# protestSign.net
KiCad netlist of a schematic drawn in EAGLE
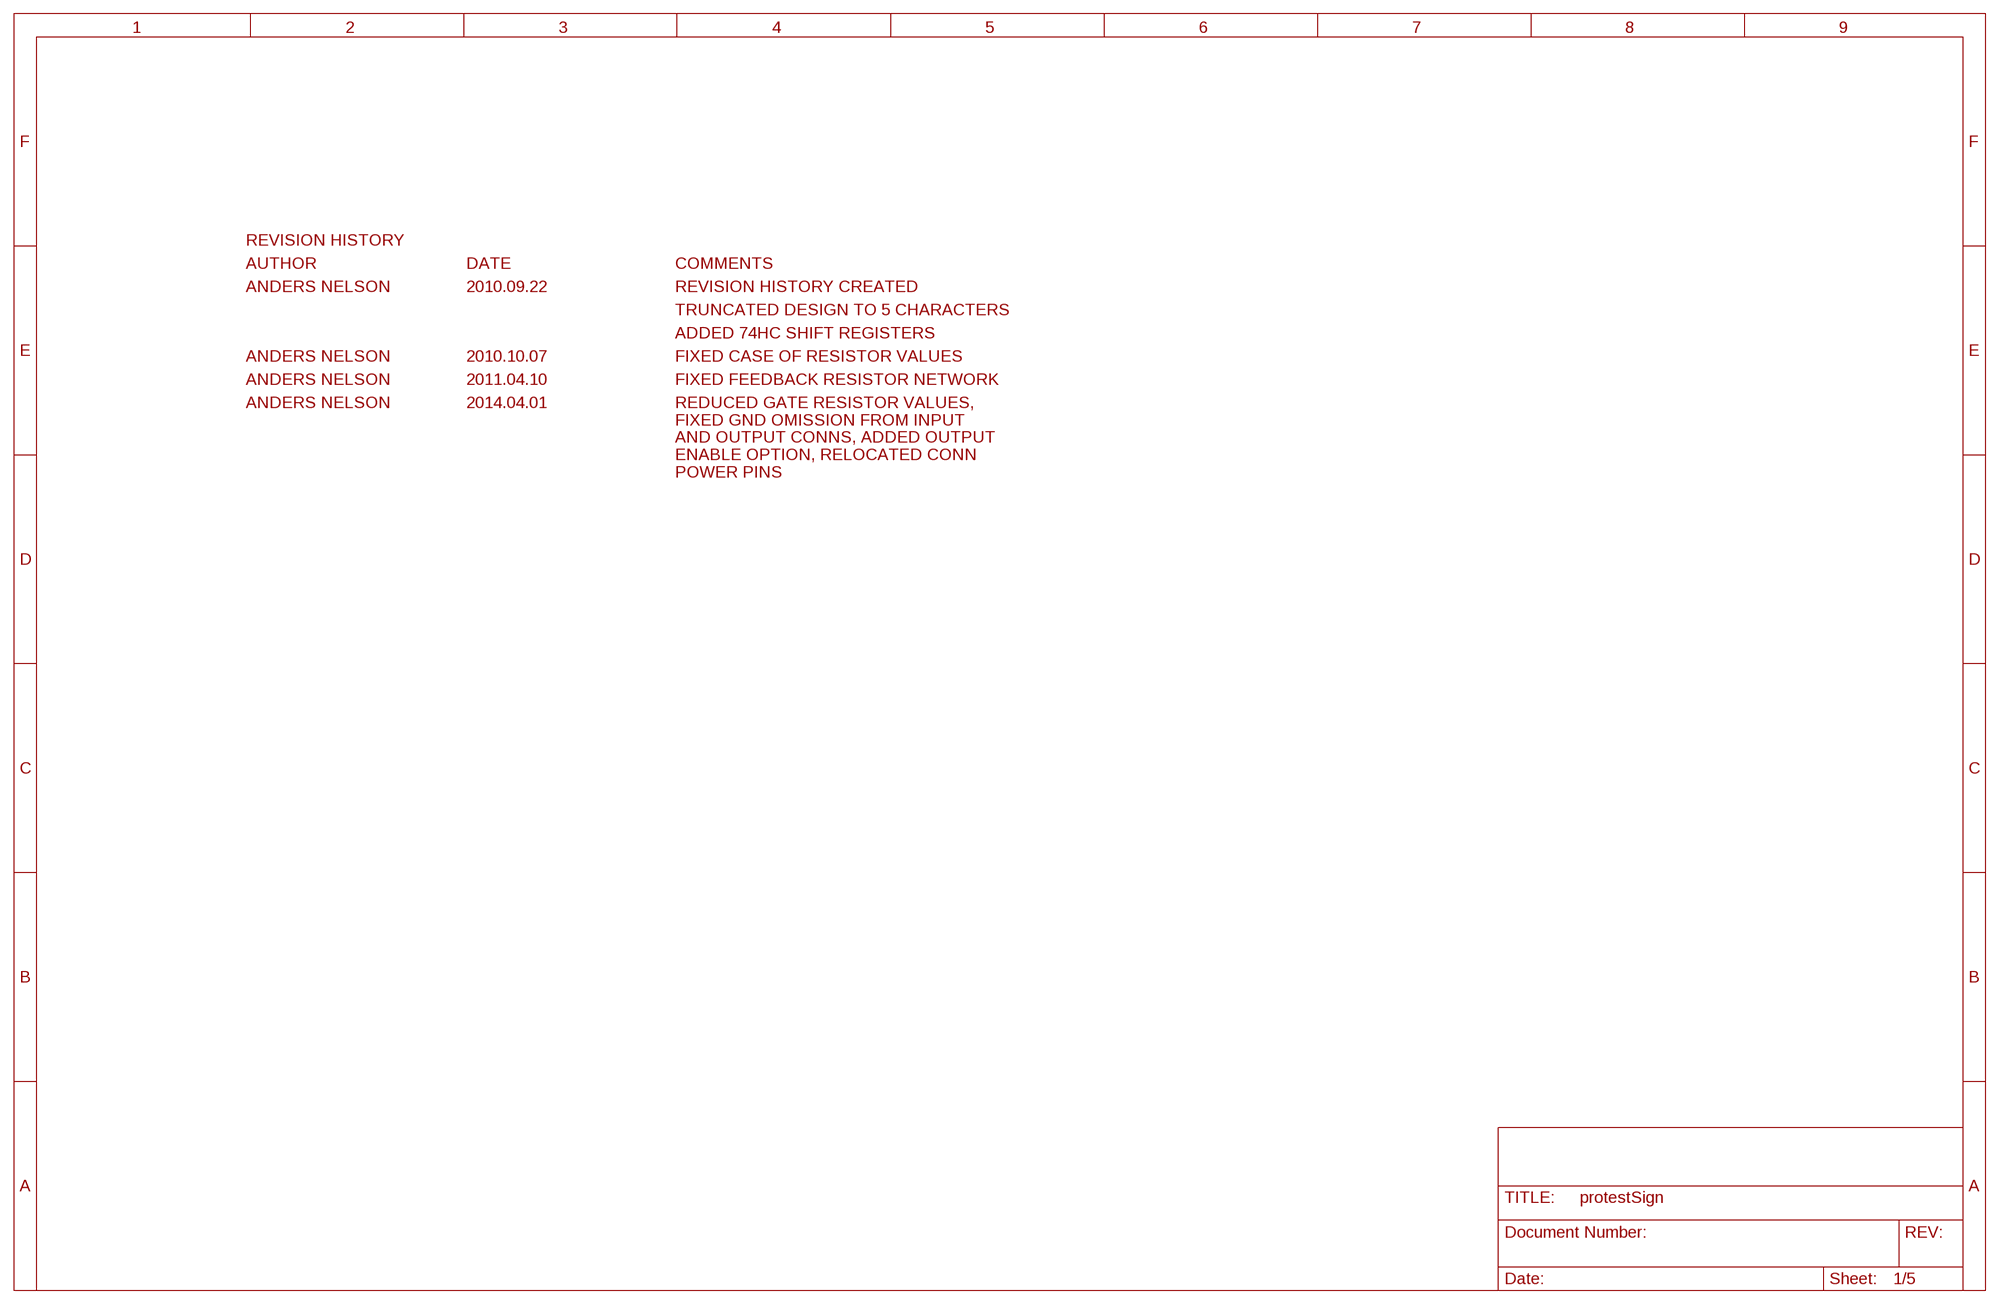
[diagram p0: schematic, sheet 1]
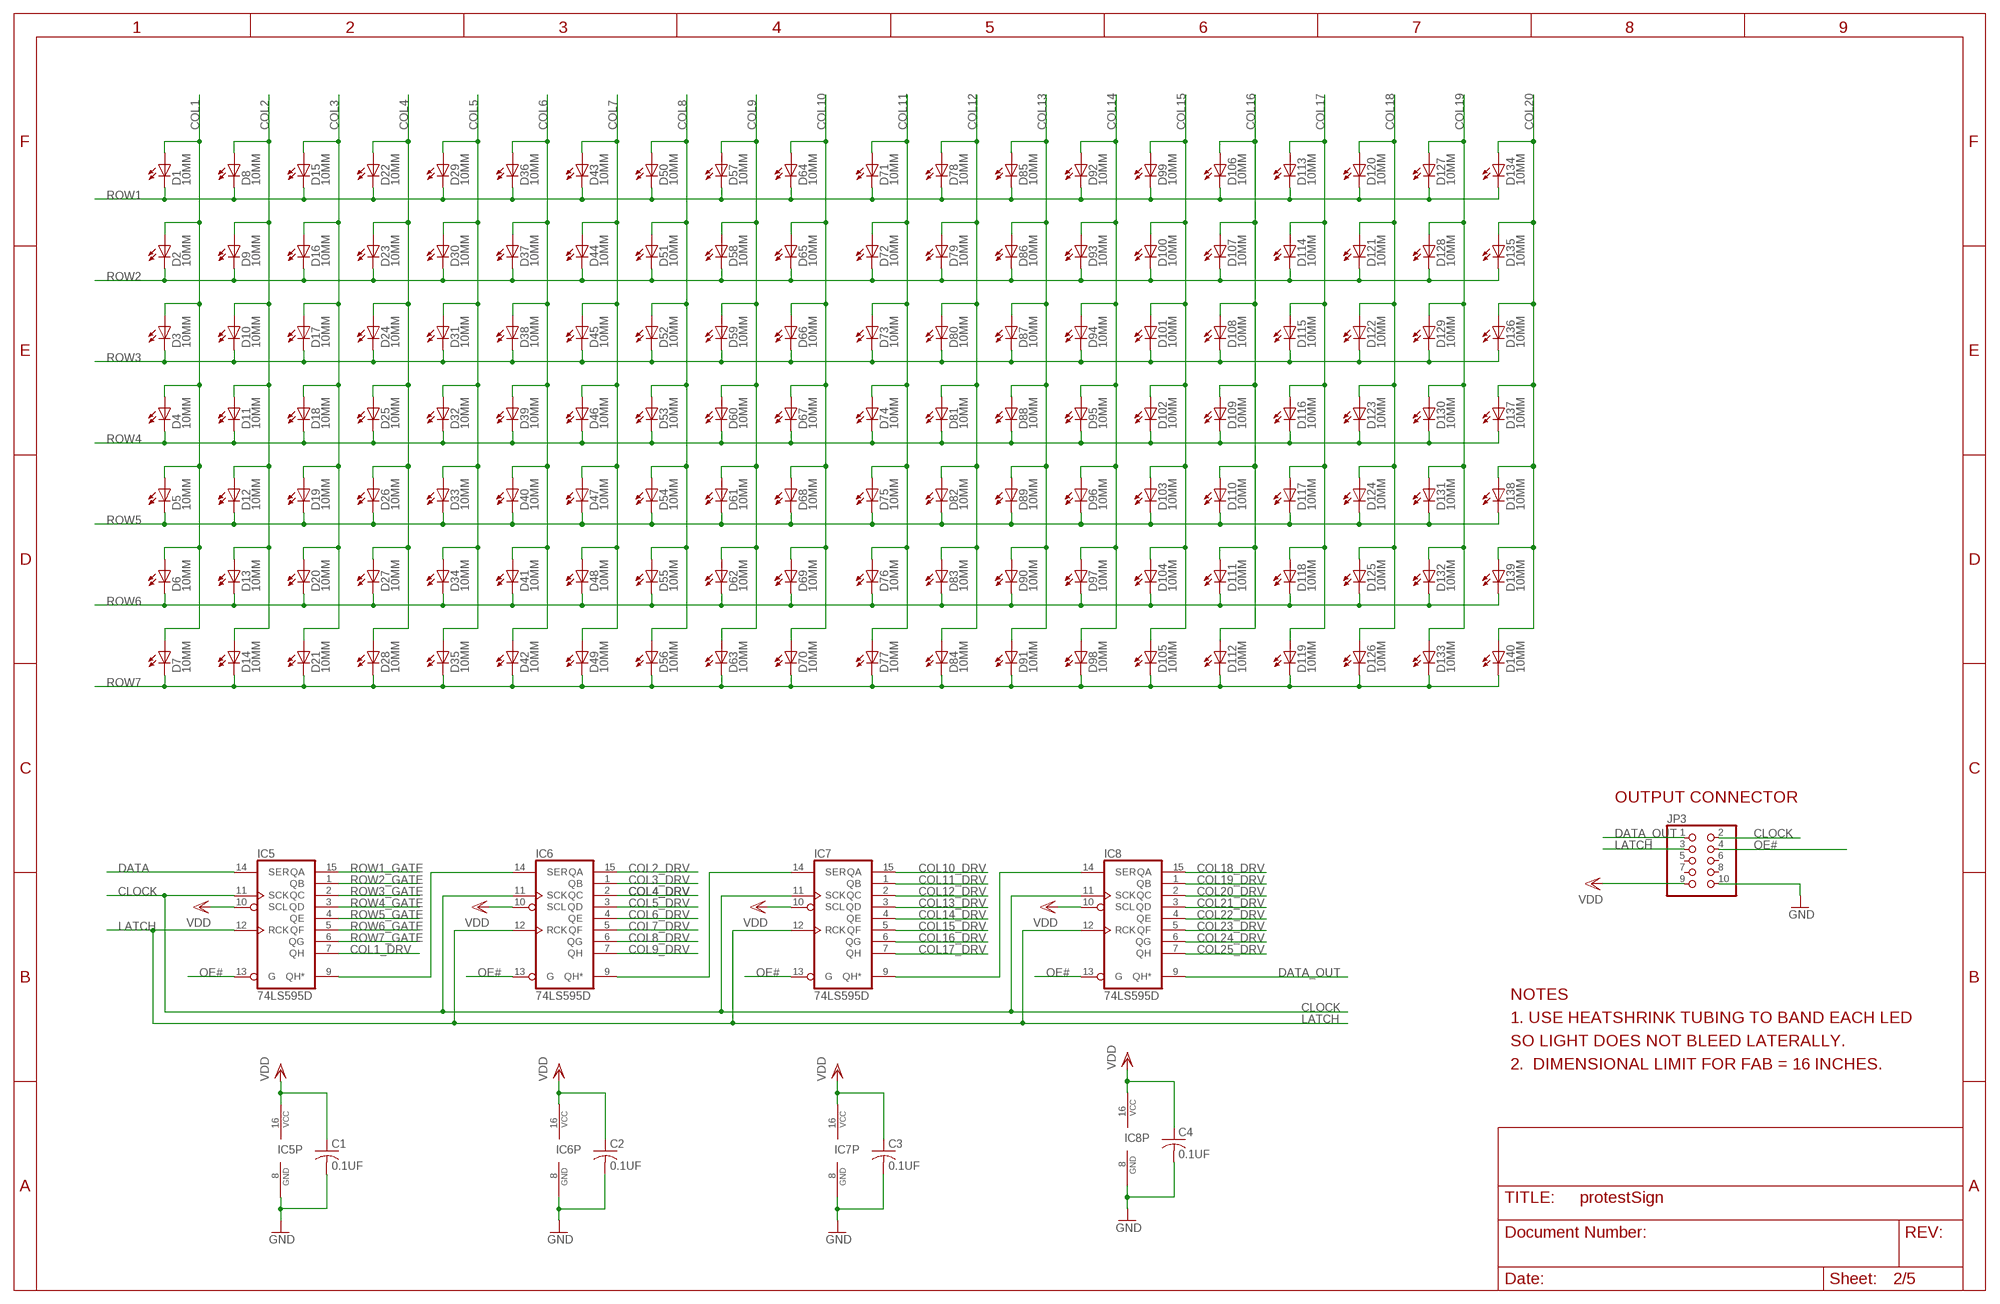
[diagram p1: schematic, sheet 2]
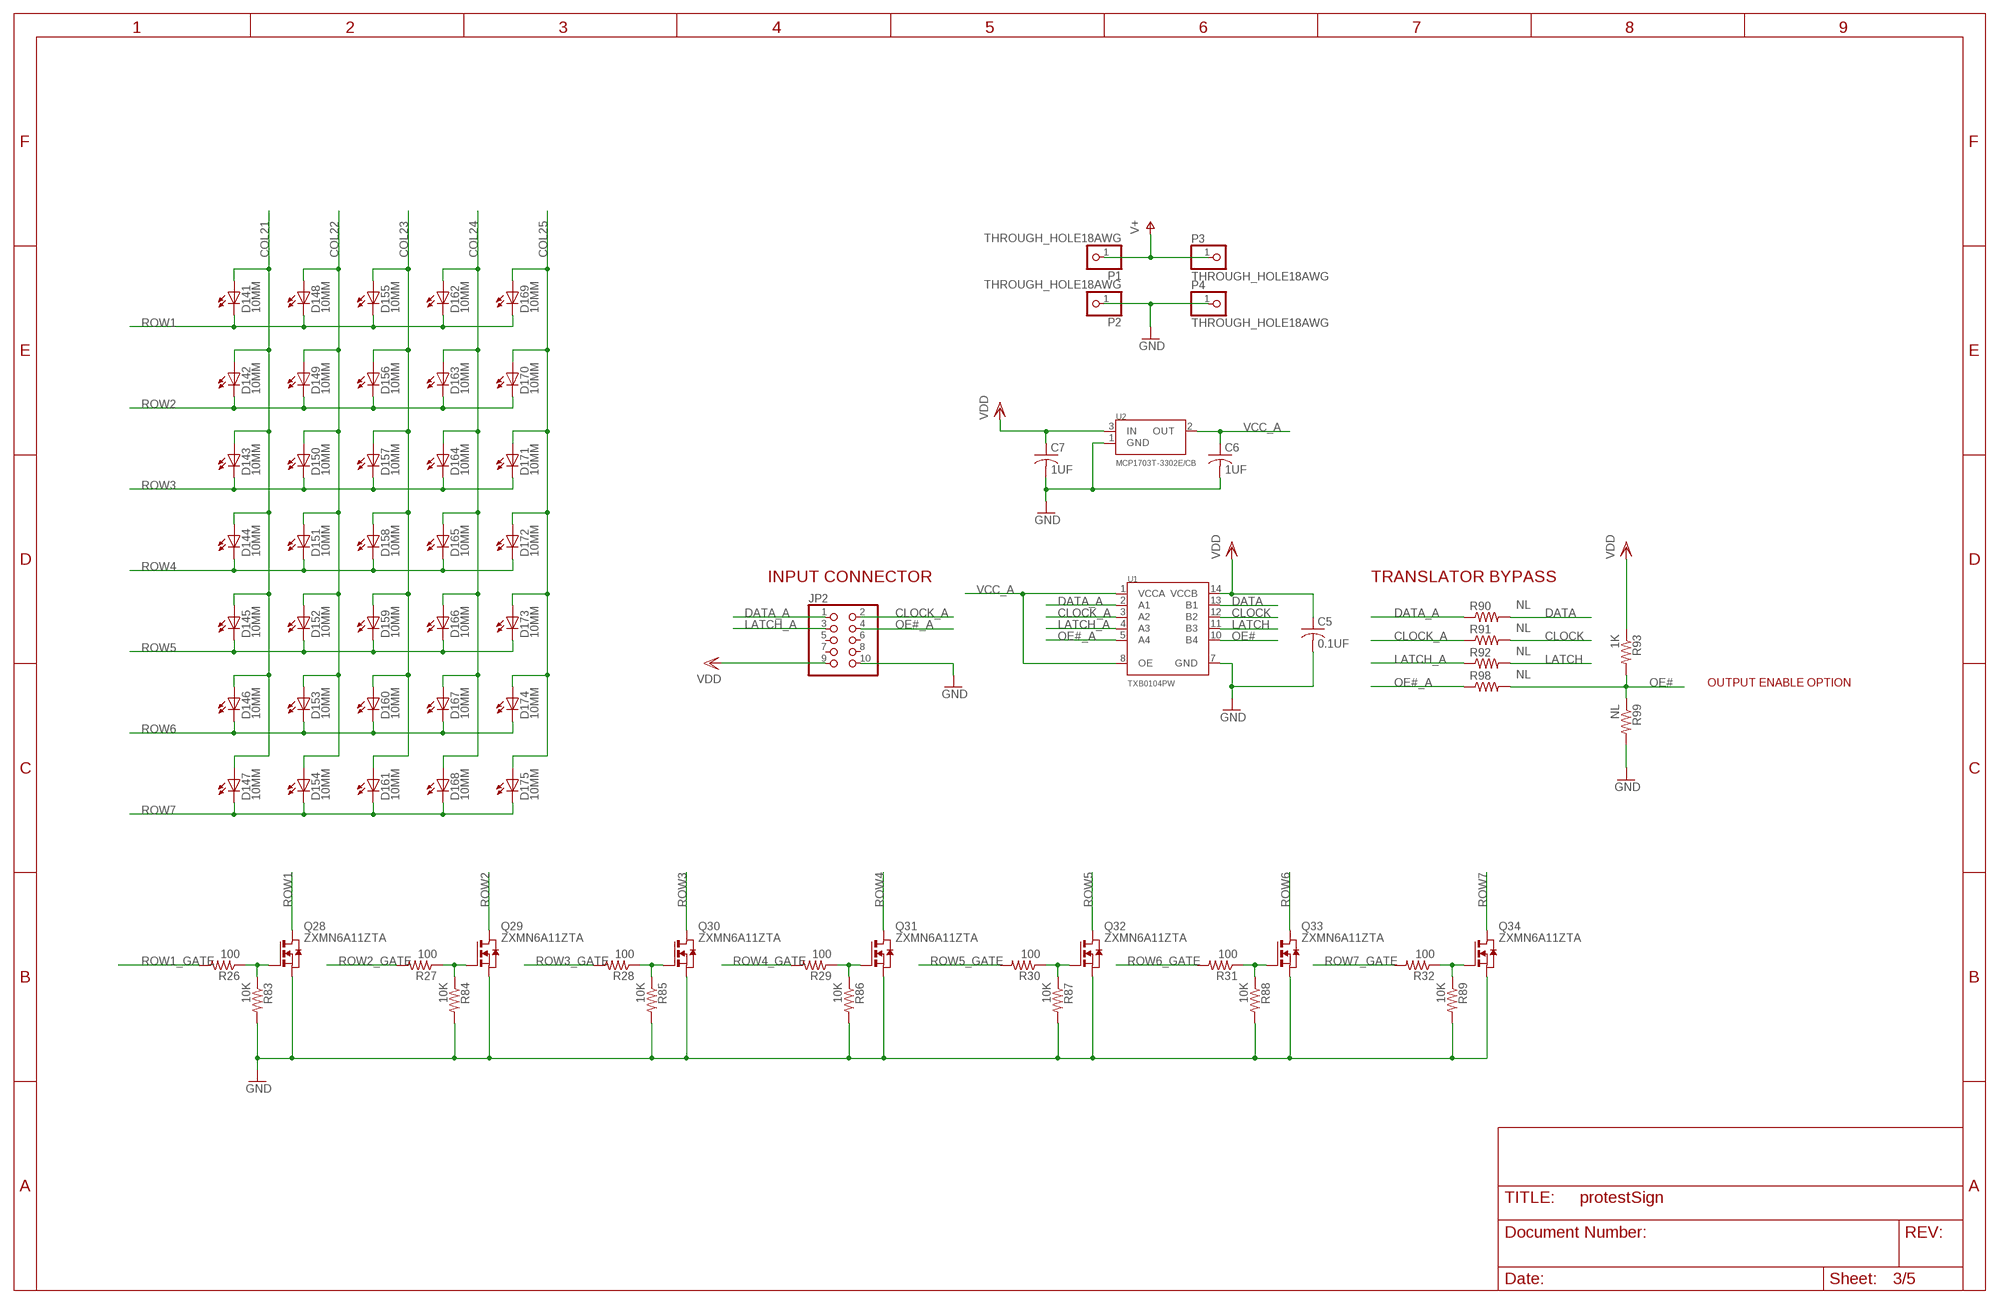
[diagram p2: schematic, sheet 3]
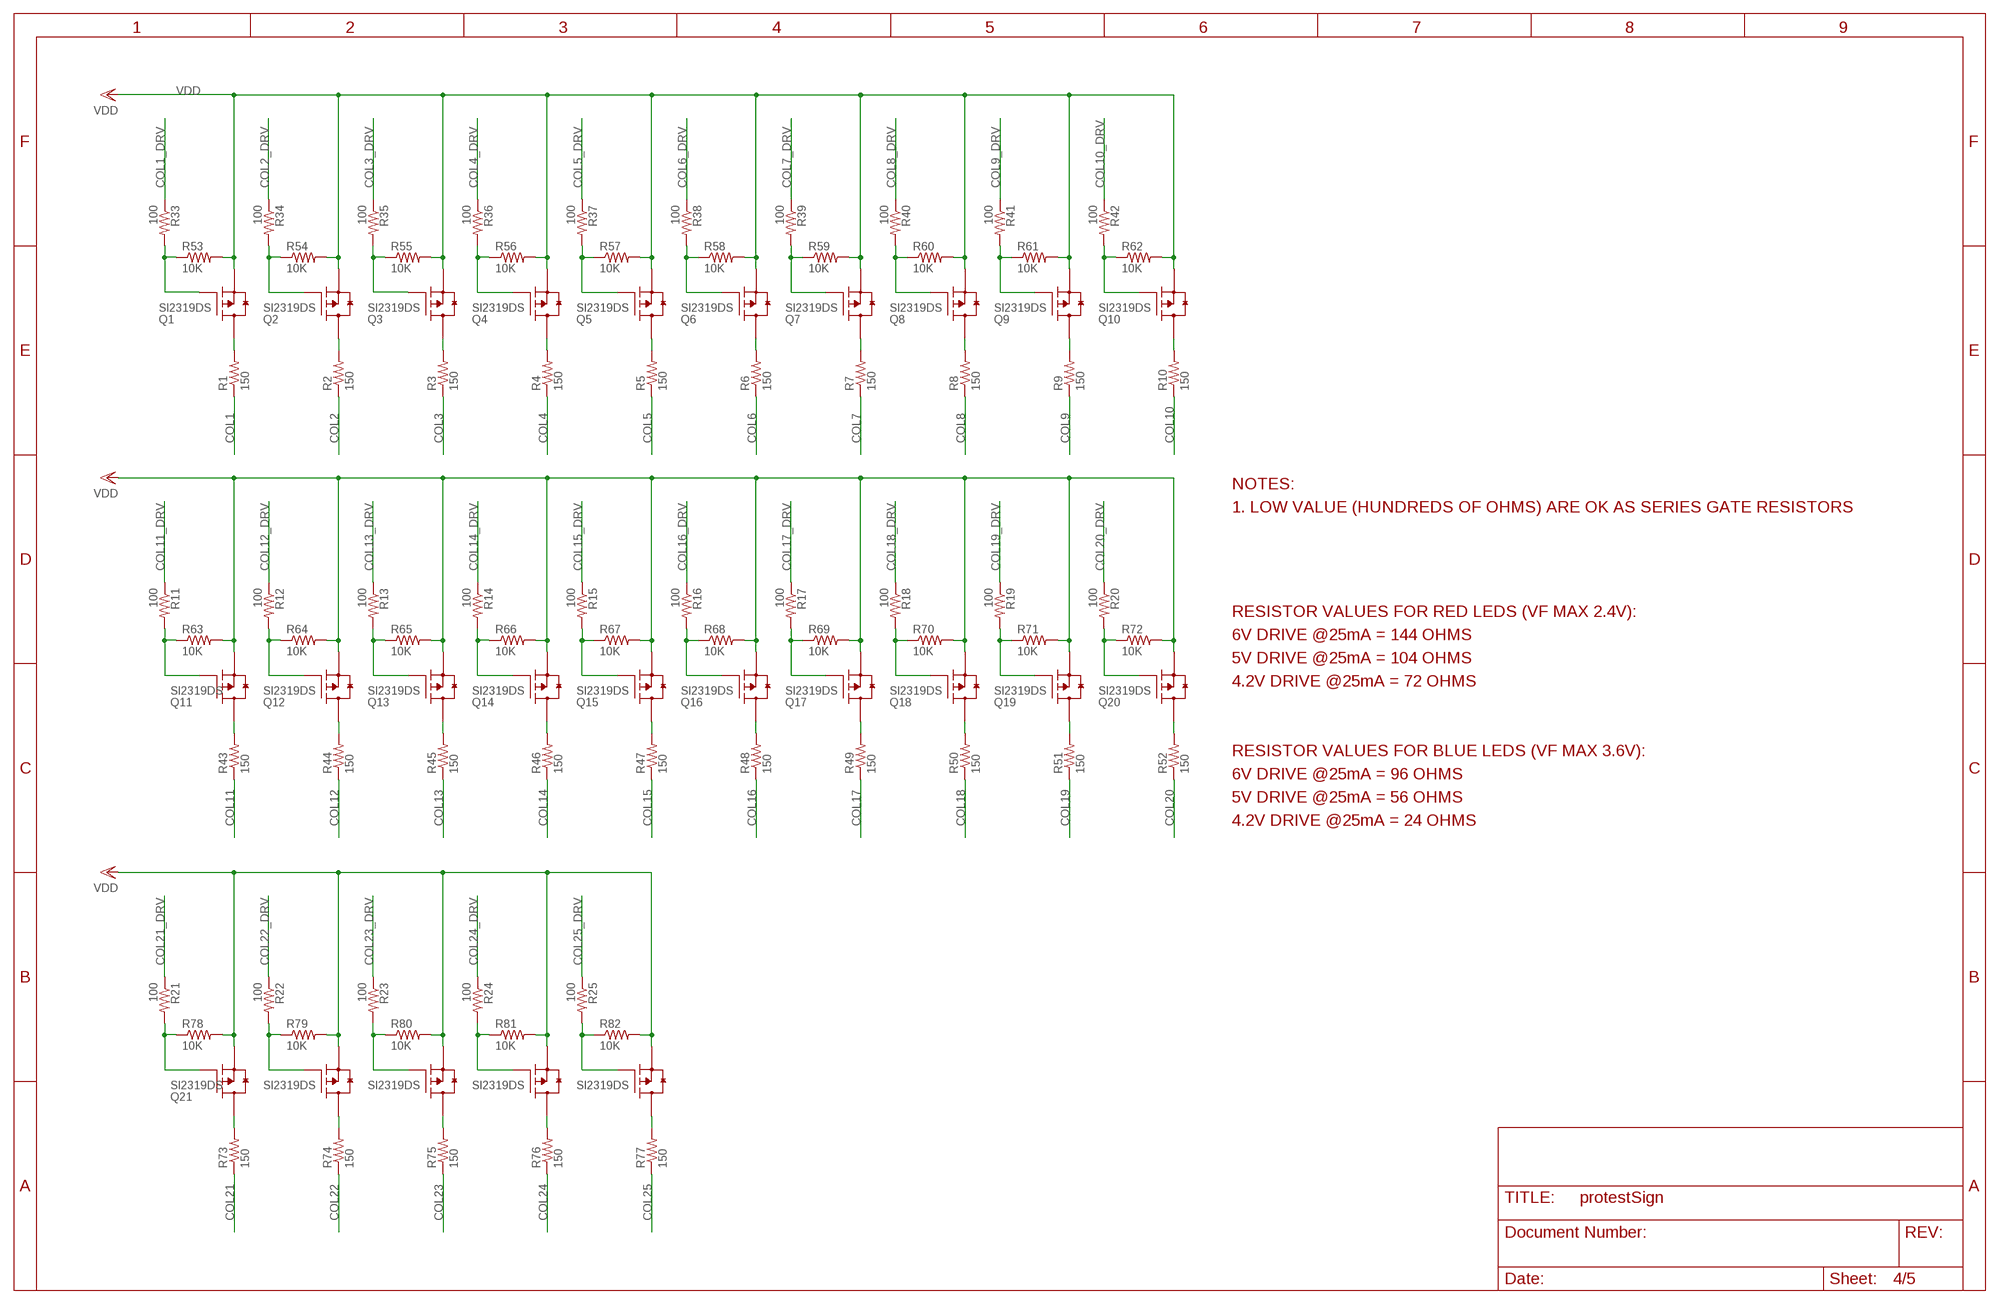
[diagram p3: schematic, sheet 4]
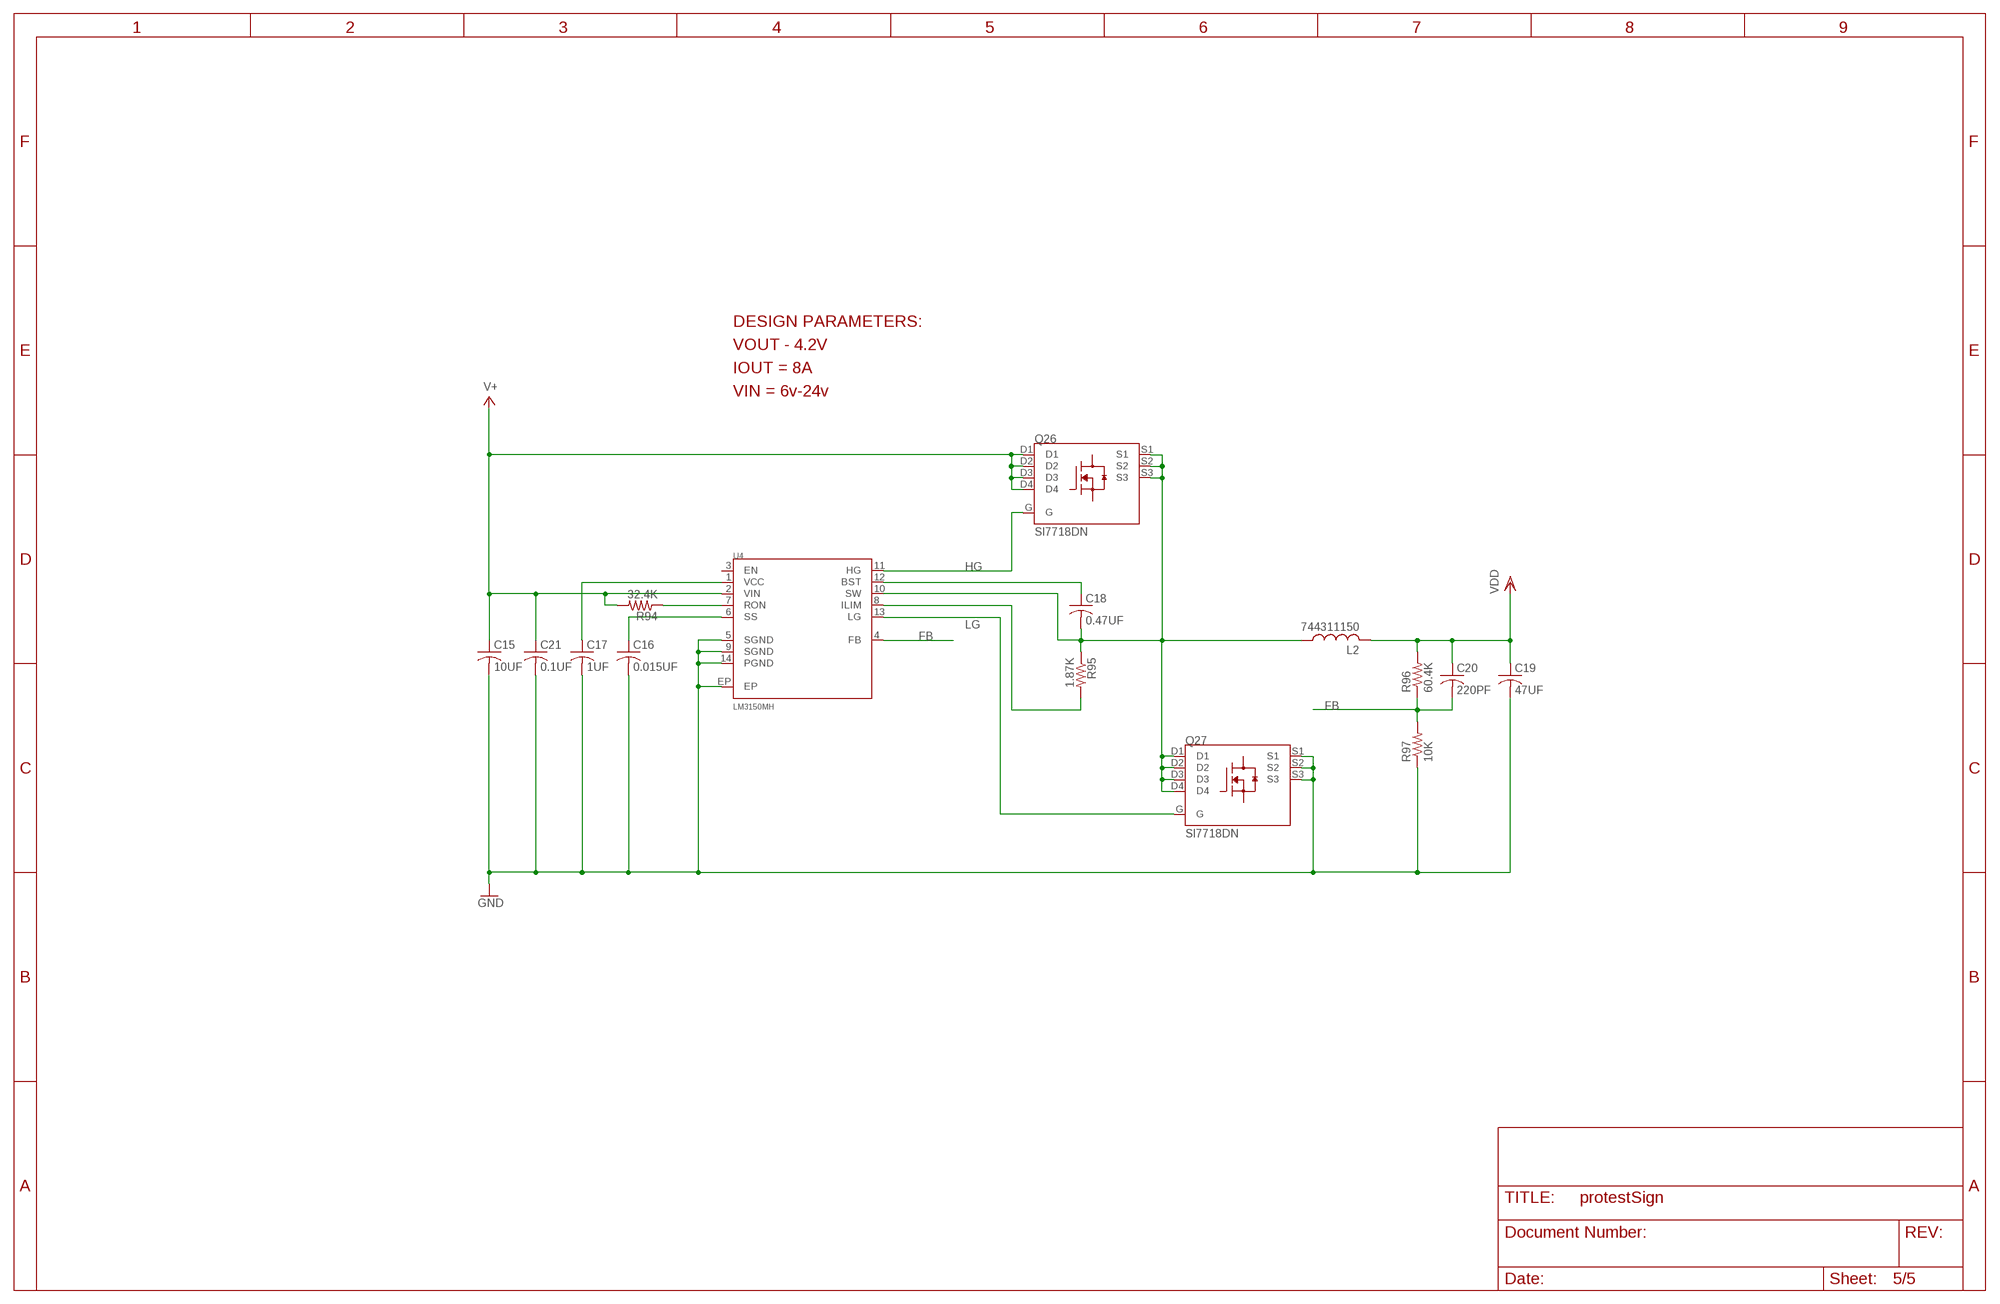
[diagram p4: schematic, sheet 5]

(export (version "E")
  (design (tool "Eeschema 10.0.6"))
  (components
    (comp (ref "Q1")
      (value "SI2319DS")
      (footprint "eagle-import:SOT23")
      (libsource (lib "eagle-import") (part "SI2319DS"))
    )
    (comp (ref "Q2")
      (value "SI2319DS")
      (footprint "eagle-import:SOT23")
      (libsource (lib "eagle-import") (part "SI2319DS"))
    )
    (comp (ref "Q3")
      (value "SI2319DS")
      (footprint "eagle-import:SOT23")
      (libsource (lib "eagle-import") (part "SI2319DS"))
    )
    (comp (ref "Q4")
      (value "SI2319DS")
      (footprint "eagle-import:SOT23")
      (libsource (lib "eagle-import") (part "SI2319DS"))
    )
    (comp (ref "Q5")
      (value "SI2319DS")
      (footprint "eagle-import:SOT23")
      (libsource (lib "eagle-import") (part "SI2319DS"))
    )
    (comp (ref "Q6")
      (value "SI2319DS")
      (footprint "eagle-import:SOT23")
      (libsource (lib "eagle-import") (part "SI2319DS"))
    )
    (comp (ref "Q7")
      (value "SI2319DS")
      (footprint "eagle-import:SOT23")
      (libsource (lib "eagle-import") (part "SI2319DS"))
    )
    (comp (ref "Q8")
      (value "SI2319DS")
      (footprint "eagle-import:SOT23")
      (libsource (lib "eagle-import") (part "SI2319DS"))
    )
    (comp (ref "Q9")
      (value "SI2319DS")
      (footprint "eagle-import:SOT23")
      (libsource (lib "eagle-import") (part "SI2319DS"))
    )
    (comp (ref "Q10")
      (value "SI2319DS")
      (footprint "eagle-import:SOT23")
      (libsource (lib "eagle-import") (part "SI2319DS"))
    )
    (comp (ref "Q11")
      (value "SI2319DS")
      (footprint "eagle-import:SOT23")
      (libsource (lib "eagle-import") (part "SI2319DS"))
    )
    (comp (ref "Q12")
      (value "SI2319DS")
      (footprint "eagle-import:SOT23")
      (libsource (lib "eagle-import") (part "SI2319DS"))
    )
    (comp (ref "Q13")
      (value "SI2319DS")
      (footprint "eagle-import:SOT23")
      (libsource (lib "eagle-import") (part "SI2319DS"))
    )
    (comp (ref "Q14")
      (value "SI2319DS")
      (footprint "eagle-import:SOT23")
      (libsource (lib "eagle-import") (part "SI2319DS"))
    )
    (comp (ref "Q15")
      (value "SI2319DS")
      (footprint "eagle-import:SOT23")
      (libsource (lib "eagle-import") (part "SI2319DS"))
    )
    (comp (ref "Q16")
      (value "SI2319DS")
      (footprint "eagle-import:SOT23")
      (libsource (lib "eagle-import") (part "SI2319DS"))
    )
    (comp (ref "Q17")
      (value "SI2319DS")
      (footprint "eagle-import:SOT23")
      (libsource (lib "eagle-import") (part "SI2319DS"))
    )
    (comp (ref "Q18")
      (value "SI2319DS")
      (footprint "eagle-import:SOT23")
      (libsource (lib "eagle-import") (part "SI2319DS"))
    )
    (comp (ref "Q19")
      (value "SI2319DS")
      (footprint "eagle-import:SOT23")
      (libsource (lib "eagle-import") (part "SI2319DS"))
    )
    (comp (ref "Q20")
      (value "SI2319DS")
      (footprint "eagle-import:SOT23")
      (libsource (lib "eagle-import") (part "SI2319DS"))
    )
    (comp (ref "Q21")
      (value "SI2319DS")
      (footprint "eagle-import:SOT23")
      (libsource (lib "eagle-import") (part "SI2319DS"))
    )
    (comp (ref "Q22")
      (value "SI2319DS")
      (footprint "eagle-import:SOT23")
      (libsource (lib "eagle-import") (part "SI2319DS"))
    )
    (comp (ref "Q23")
      (value "SI2319DS")
      (footprint "eagle-import:SOT23")
      (libsource (lib "eagle-import") (part "SI2319DS"))
    )
    (comp (ref "Q24")
      (value "SI2319DS")
      (footprint "eagle-import:SOT23")
      (libsource (lib "eagle-import") (part "SI2319DS"))
    )
    (comp (ref "Q25")
      (value "SI2319DS")
      (footprint "eagle-import:SOT23")
      (libsource (lib "eagle-import") (part "SI2319DS"))
    )
    (comp (ref "R1")
      (value "150")
      (footprint "eagle-import:M0805")
      (libsource (lib "eagle-import") (part "R-US_M0805"))
    )
    (comp (ref "R2")
      (value "150")
      (footprint "eagle-import:M0805")
      (libsource (lib "eagle-import") (part "R-US_M0805"))
    )
    (comp (ref "R3")
      (value "150")
      (footprint "eagle-import:M0805")
      (libsource (lib "eagle-import") (part "R-US_M0805"))
    )
    (comp (ref "R4")
      (value "150")
      (footprint "eagle-import:M0805")
      (libsource (lib "eagle-import") (part "R-US_M0805"))
    )
    (comp (ref "R5")
      (value "150")
      (footprint "eagle-import:M0805")
      (libsource (lib "eagle-import") (part "R-US_M0805"))
    )
    (comp (ref "R6")
      (value "150")
      (footprint "eagle-import:M0805")
      (libsource (lib "eagle-import") (part "R-US_M0805"))
    )
    (comp (ref "R7")
      (value "150")
      (footprint "eagle-import:M0805")
      (libsource (lib "eagle-import") (part "R-US_M0805"))
    )
    (comp (ref "R8")
      (value "150")
      (footprint "eagle-import:M0805")
      (libsource (lib "eagle-import") (part "R-US_M0805"))
    )
    (comp (ref "R9")
      (value "150")
      (footprint "eagle-import:M0805")
      (libsource (lib "eagle-import") (part "R-US_M0805"))
    )
    (comp (ref "R10")
      (value "150")
      (footprint "eagle-import:M0805")
      (libsource (lib "eagle-import") (part "R-US_M0805"))
    )
    (comp (ref "R11")
      (value "100")
      (footprint "eagle-import:R0603")
      (libsource (lib "eagle-import") (part "R-US_R0603"))
    )
    (comp (ref "R12")
      (value "100")
      (footprint "eagle-import:R0603")
      (libsource (lib "eagle-import") (part "R-US_R0603"))
    )
    (comp (ref "R13")
      (value "100")
      (footprint "eagle-import:R0603")
      (libsource (lib "eagle-import") (part "R-US_R0603"))
    )
    (comp (ref "R14")
      (value "100")
      (footprint "eagle-import:R0603")
      (libsource (lib "eagle-import") (part "R-US_R0603"))
    )
    (comp (ref "R15")
      (value "100")
      (footprint "eagle-import:R0603")
      (libsource (lib "eagle-import") (part "R-US_R0603"))
    )
    (comp (ref "R16")
      (value "100")
      (footprint "eagle-import:R0603")
      (libsource (lib "eagle-import") (part "R-US_R0603"))
    )
    (comp (ref "R17")
      (value "100")
      (footprint "eagle-import:R0603")
      (libsource (lib "eagle-import") (part "R-US_R0603"))
    )
    (comp (ref "R18")
      (value "100")
      (footprint "eagle-import:R0603")
      (libsource (lib "eagle-import") (part "R-US_R0603"))
    )
    (comp (ref "R19")
      (value "100")
      (footprint "eagle-import:R0603")
      (libsource (lib "eagle-import") (part "R-US_R0603"))
    )
    (comp (ref "R20")
      (value "100")
      (footprint "eagle-import:R0603")
      (libsource (lib "eagle-import") (part "R-US_R0603"))
    )
    (comp (ref "R21")
      (value "100")
      (footprint "eagle-import:R0603")
      (libsource (lib "eagle-import") (part "R-US_R0603"))
    )
    (comp (ref "R22")
      (value "100")
      (footprint "eagle-import:R0603")
      (libsource (lib "eagle-import") (part "R-US_R0603"))
    )
    (comp (ref "R23")
      (value "100")
      (footprint "eagle-import:R0603")
      (libsource (lib "eagle-import") (part "R-US_R0603"))
    )
    (comp (ref "R24")
      (value "100")
      (footprint "eagle-import:R0603")
      (libsource (lib "eagle-import") (part "R-US_R0603"))
    )
    (comp (ref "R25")
      (value "100")
      (footprint "eagle-import:R0603")
      (libsource (lib "eagle-import") (part "R-US_R0603"))
    )
    (comp (ref "R33")
      (value "100")
      (footprint "eagle-import:R0603")
      (libsource (lib "eagle-import") (part "R-US_R0603"))
    )
    (comp (ref "R34")
      (value "100")
      (footprint "eagle-import:R0603")
      (libsource (lib "eagle-import") (part "R-US_R0603"))
    )
    (comp (ref "R35")
      (value "100")
      (footprint "eagle-import:R0603")
      (libsource (lib "eagle-import") (part "R-US_R0603"))
    )
    (comp (ref "R36")
      (value "100")
      (footprint "eagle-import:R0603")
      (libsource (lib "eagle-import") (part "R-US_R0603"))
    )
    (comp (ref "R37")
      (value "100")
      (footprint "eagle-import:R0603")
      (libsource (lib "eagle-import") (part "R-US_R0603"))
    )
    (comp (ref "R38")
      (value "100")
      (footprint "eagle-import:R0603")
      (libsource (lib "eagle-import") (part "R-US_R0603"))
    )
    (comp (ref "R39")
      (value "100")
      (footprint "eagle-import:R0603")
      (libsource (lib "eagle-import") (part "R-US_R0603"))
    )
    (comp (ref "R40")
      (value "100")
      (footprint "eagle-import:R0603")
      (libsource (lib "eagle-import") (part "R-US_R0603"))
    )
    (comp (ref "R41")
      (value "100")
      (footprint "eagle-import:R0603")
      (libsource (lib "eagle-import") (part "R-US_R0603"))
    )
    (comp (ref "R42")
      (value "100")
      (footprint "eagle-import:R0603")
      (libsource (lib "eagle-import") (part "R-US_R0603"))
    )
    (comp (ref "R43")
      (value "150")
      (footprint "eagle-import:M0805")
      (libsource (lib "eagle-import") (part "R-US_M0805"))
    )
    (comp (ref "R44")
      (value "150")
      (footprint "eagle-import:M0805")
      (libsource (lib "eagle-import") (part "R-US_M0805"))
    )
    (comp (ref "R45")
      (value "150")
      (footprint "eagle-import:M0805")
      (libsource (lib "eagle-import") (part "R-US_M0805"))
    )
    (comp (ref "R46")
      (value "150")
      (footprint "eagle-import:M0805")
      (libsource (lib "eagle-import") (part "R-US_M0805"))
    )
    (comp (ref "R47")
      (value "150")
      (footprint "eagle-import:M0805")
      (libsource (lib "eagle-import") (part "R-US_M0805"))
    )
    (comp (ref "R48")
      (value "150")
      (footprint "eagle-import:M0805")
      (libsource (lib "eagle-import") (part "R-US_M0805"))
    )
    (comp (ref "R49")
      (value "150")
      (footprint "eagle-import:M0805")
      (libsource (lib "eagle-import") (part "R-US_M0805"))
    )
    (comp (ref "R50")
      (value "150")
      (footprint "eagle-import:M0805")
      (libsource (lib "eagle-import") (part "R-US_M0805"))
    )
    (comp (ref "R51")
      (value "150")
      (footprint "eagle-import:M0805")
      (libsource (lib "eagle-import") (part "R-US_M0805"))
    )
    (comp (ref "R52")
      (value "150")
      (footprint "eagle-import:M0805")
      (libsource (lib "eagle-import") (part "R-US_M0805"))
    )
    (comp (ref "R53")
      (value "10K")
      (footprint "eagle-import:R0603")
      (libsource (lib "eagle-import") (part "R-US_R0603"))
    )
    (comp (ref "R54")
      (value "10K")
      (footprint "eagle-import:R0603")
      (libsource (lib "eagle-import") (part "R-US_R0603"))
    )
    (comp (ref "R55")
      (value "10K")
      (footprint "eagle-import:R0603")
      (libsource (lib "eagle-import") (part "R-US_R0603"))
    )
    (comp (ref "R56")
      (value "10K")
      (footprint "eagle-import:R0603")
      (libsource (lib "eagle-import") (part "R-US_R0603"))
    )
    (comp (ref "R57")
      (value "10K")
      (footprint "eagle-import:R0603")
      (libsource (lib "eagle-import") (part "R-US_R0603"))
    )
    (comp (ref "R58")
      (value "10K")
      (footprint "eagle-import:R0603")
      (libsource (lib "eagle-import") (part "R-US_R0603"))
    )
    (comp (ref "R59")
      (value "10K")
      (footprint "eagle-import:R0603")
      (libsource (lib "eagle-import") (part "R-US_R0603"))
    )
    (comp (ref "R60")
      (value "10K")
      (footprint "eagle-import:R0603")
      (libsource (lib "eagle-import") (part "R-US_R0603"))
    )
    (comp (ref "R61")
      (value "10K")
      (footprint "eagle-import:R0603")
      (libsource (lib "eagle-import") (part "R-US_R0603"))
    )
    (comp (ref "R62")
      (value "10K")
      (footprint "eagle-import:R0603")
      (libsource (lib "eagle-import") (part "R-US_R0603"))
    )
    (comp (ref "R63")
      (value "10K")
      (footprint "eagle-import:R0603")
      (libsource (lib "eagle-import") (part "R-US_R0603"))
    )
    (comp (ref "R64")
      (value "10K")
      (footprint "eagle-import:R0603")
      (libsource (lib "eagle-import") (part "R-US_R0603"))
    )
    (comp (ref "R65")
      (value "10K")
      (footprint "eagle-import:R0603")
      (libsource (lib "eagle-import") (part "R-US_R0603"))
    )
    (comp (ref "R66")
      (value "10K")
      (footprint "eagle-import:R0603")
      (libsource (lib "eagle-import") (part "R-US_R0603"))
    )
    (comp (ref "R67")
      (value "10K")
      (footprint "eagle-import:R0603")
      (libsource (lib "eagle-import") (part "R-US_R0603"))
    )
    (comp (ref "R68")
      (value "10K")
      (footprint "eagle-import:R0603")
      (libsource (lib "eagle-import") (part "R-US_R0603"))
    )
    (comp (ref "R69")
      (value "10K")
      (footprint "eagle-import:R0603")
      (libsource (lib "eagle-import") (part "R-US_R0603"))
    )
    (comp (ref "R70")
      (value "10K")
      (footprint "eagle-import:R0603")
      (libsource (lib "eagle-import") (part "R-US_R0603"))
    )
    (comp (ref "R71")
      (value "10K")
      (footprint "eagle-import:R0603")
      (libsource (lib "eagle-import") (part "R-US_R0603"))
    )
    (comp (ref "R72")
      (value "10K")
      (footprint "eagle-import:R0603")
      (libsource (lib "eagle-import") (part "R-US_R0603"))
    )
    (comp (ref "R73")
      (value "150")
      (footprint "eagle-import:M0805")
      (libsource (lib "eagle-import") (part "R-US_M0805"))
    )
    (comp (ref "R74")
      (value "150")
      (footprint "eagle-import:M0805")
      (libsource (lib "eagle-import") (part "R-US_M0805"))
    )
    (comp (ref "R75")
      (value "150")
      (footprint "eagle-import:M0805")
      (libsource (lib "eagle-import") (part "R-US_M0805"))
    )
    (comp (ref "R76")
      (value "150")
      (footprint "eagle-import:M0805")
      (libsource (lib "eagle-import") (part "R-US_M0805"))
    )
    (comp (ref "R77")
      (value "150")
      (footprint "eagle-import:M0805")
      (libsource (lib "eagle-import") (part "R-US_M0805"))
    )
    (comp (ref "R78")
      (value "10K")
      (footprint "eagle-import:R0603")
      (libsource (lib "eagle-import") (part "R-US_R0603"))
    )
    (comp (ref "R79")
      (value "10K")
      (footprint "eagle-import:R0603")
      (libsource (lib "eagle-import") (part "R-US_R0603"))
    )
    (comp (ref "R80")
      (value "10K")
      (footprint "eagle-import:R0603")
      (libsource (lib "eagle-import") (part "R-US_R0603"))
    )
    (comp (ref "R81")
      (value "10K")
      (footprint "eagle-import:R0603")
      (libsource (lib "eagle-import") (part "R-US_R0603"))
    )
    (comp (ref "R82")
      (value "10K")
      (footprint "eagle-import:R0603")
      (libsource (lib "eagle-import") (part "R-US_R0603"))
    )
    (comp (ref "C15")
      (value "10UF")
      (footprint "eagle-import:C1210")
      (libsource (lib "eagle-import") (part "C-USC1210"))
    )
    (comp (ref "C16")
      (value "0.015UF")
      (footprint "eagle-import:C0603")
      (libsource (lib "eagle-import") (part "C-USC0603"))
    )
    (comp (ref "C17")
      (value "1UF")
      (footprint "eagle-import:C0603")
      (libsource (lib "eagle-import") (part "C-USC0603"))
    )
    (comp (ref "C18")
      (value "0.47UF")
      (footprint "eagle-import:C0603")
      (libsource (lib "eagle-import") (part "C-USC0603"))
    )
    (comp (ref "C19")
      (value "47UF")
      (footprint "eagle-import:C1210")
      (libsource (lib "eagle-import") (part "C-USC1210"))
    )
    (comp (ref "C20")
      (value "220PF")
      (footprint "eagle-import:C0603")
      (libsource (lib "eagle-import") (part "C-USC0603"))
    )
    (comp (ref "C21")
      (value "0.1UF")
      (footprint "eagle-import:C0603")
      (libsource (lib "eagle-import") (part "C-USC0603"))
    )
    (comp (ref "L2")
      (value "744311150")
      (footprint "eagle-import:744311150")
      (libsource (lib "eagle-import") (part "744311150"))
    )
    (comp (ref "Q26")
      (value "SI7718DN")
      (footprint "eagle-import:POWERPAK_1212_8")
      (libsource (lib "eagle-import") (part "SI7718DN"))
    )
    (comp (ref "Q27")
      (value "SI7718DN")
      (footprint "eagle-import:POWERPAK_1212_8")
      (libsource (lib "eagle-import") (part "SI7718DN"))
    )
    (comp (ref "R94")
      (value "32.4K")
      (footprint "eagle-import:R0603")
      (libsource (lib "eagle-import") (part "R-US_R0603"))
    )
    (comp (ref "R95")
      (value "1.87K")
      (footprint "eagle-import:R0603")
      (libsource (lib "eagle-import") (part "R-US_R0603"))
    )
    (comp (ref "R96")
      (value "60.4K")
      (footprint "eagle-import:R0603")
      (libsource (lib "eagle-import") (part "R-US_R0603"))
    )
    (comp (ref "R97")
      (value "10K")
      (footprint "eagle-import:R0603")
      (libsource (lib "eagle-import") (part "R-US_R0603"))
    )
    (comp (ref "U4")
      (value "LM3150MH")
      (footprint "eagle-import:TSSOP14_EP")
      (libsource (lib "eagle-import") (part "LM3150MH"))
    )
    (comp (ref "C1")
      (value "0.1UF")
      (footprint "eagle-import:C0603")
      (libsource (lib "eagle-import") (part "C-USC0603"))
    )
    (comp (ref "C2")
      (value "0.1UF")
      (footprint "eagle-import:C0603")
      (libsource (lib "eagle-import") (part "C-USC0603"))
    )
    (comp (ref "C3")
      (value "0.1UF")
      (footprint "eagle-import:C0603")
      (libsource (lib "eagle-import") (part "C-USC0603"))
    )
    (comp (ref "C4")
      (value "0.1UF")
      (footprint "eagle-import:C0603")
      (libsource (lib "eagle-import") (part "C-USC0603"))
    )
    (comp (ref "D1")
      (value "10MM")
      (footprint "eagle-import:LED_10MM")
      (libsource (lib "eagle-import") (part "10MM"))
    )
    (comp (ref "D2")
      (value "10MM")
      (footprint "eagle-import:LED_10MM")
      (libsource (lib "eagle-import") (part "10MM"))
    )
    (comp (ref "D3")
      (value "10MM")
      (footprint "eagle-import:LED_10MM")
      (libsource (lib "eagle-import") (part "10MM"))
    )
    (comp (ref "D4")
      (value "10MM")
      (footprint "eagle-import:LED_10MM")
      (libsource (lib "eagle-import") (part "10MM"))
    )
    (comp (ref "D5")
      (value "10MM")
      (footprint "eagle-import:LED_10MM")
      (libsource (lib "eagle-import") (part "10MM"))
    )
    (comp (ref "D6")
      (value "10MM")
      (footprint "eagle-import:LED_10MM")
      (libsource (lib "eagle-import") (part "10MM"))
    )
    (comp (ref "D7")
      (value "10MM")
      (footprint "eagle-import:LED_10MM")
      (libsource (lib "eagle-import") (part "10MM"))
    )
    (comp (ref "D8")
      (value "10MM")
      (footprint "eagle-import:LED_10MM")
      (libsource (lib "eagle-import") (part "10MM"))
    )
    (comp (ref "D9")
      (value "10MM")
      (footprint "eagle-import:LED_10MM")
      (libsource (lib "eagle-import") (part "10MM"))
    )
    (comp (ref "D10")
      (value "10MM")
      (footprint "eagle-import:LED_10MM")
      (libsource (lib "eagle-import") (part "10MM"))
    )
    (comp (ref "D11")
      (value "10MM")
      (footprint "eagle-import:LED_10MM")
      (libsource (lib "eagle-import") (part "10MM"))
    )
    (comp (ref "D12")
      (value "10MM")
      (footprint "eagle-import:LED_10MM")
      (libsource (lib "eagle-import") (part "10MM"))
    )
    (comp (ref "D13")
      (value "10MM")
      (footprint "eagle-import:LED_10MM")
      (libsource (lib "eagle-import") (part "10MM"))
    )
    (comp (ref "D14")
      (value "10MM")
      (footprint "eagle-import:LED_10MM")
      (libsource (lib "eagle-import") (part "10MM"))
    )
    (comp (ref "D15")
      (value "10MM")
      (footprint "eagle-import:LED_10MM")
      (libsource (lib "eagle-import") (part "10MM"))
    )
    (comp (ref "D16")
      (value "10MM")
      (footprint "eagle-import:LED_10MM")
      (libsource (lib "eagle-import") (part "10MM"))
    )
    (comp (ref "D17")
      (value "10MM")
      (footprint "eagle-import:LED_10MM")
      (libsource (lib "eagle-import") (part "10MM"))
    )
    (comp (ref "D18")
      (value "10MM")
      (footprint "eagle-import:LED_10MM")
      (libsource (lib "eagle-import") (part "10MM"))
    )
    (comp (ref "D19")
      (value "10MM")
      (footprint "eagle-import:LED_10MM")
      (libsource (lib "eagle-import") (part "10MM"))
    )
    (comp (ref "D20")
      (value "10MM")
      (footprint "eagle-import:LED_10MM")
      (libsource (lib "eagle-import") (part "10MM"))
    )
    (comp (ref "D21")
      (value "10MM")
      (footprint "eagle-import:LED_10MM")
      (libsource (lib "eagle-import") (part "10MM"))
    )
    (comp (ref "D22")
      (value "10MM")
      (footprint "eagle-import:LED_10MM")
      (libsource (lib "eagle-import") (part "10MM"))
    )
    (comp (ref "D23")
      (value "10MM")
      (footprint "eagle-import:LED_10MM")
      (libsource (lib "eagle-import") (part "10MM"))
    )
    (comp (ref "D24")
      (value "10MM")
      (footprint "eagle-import:LED_10MM")
      (libsource (lib "eagle-import") (part "10MM"))
    )
    (comp (ref "D25")
      (value "10MM")
      (footprint "eagle-import:LED_10MM")
      (libsource (lib "eagle-import") (part "10MM"))
    )
    (comp (ref "D26")
      (value "10MM")
      (footprint "eagle-import:LED_10MM")
      (libsource (lib "eagle-import") (part "10MM"))
    )
    (comp (ref "D27")
      (value "10MM")
      (footprint "eagle-import:LED_10MM")
      (libsource (lib "eagle-import") (part "10MM"))
    )
    (comp (ref "D28")
      (value "10MM")
      (footprint "eagle-import:LED_10MM")
      (libsource (lib "eagle-import") (part "10MM"))
    )
    (comp (ref "D29")
      (value "10MM")
      (footprint "eagle-import:LED_10MM")
      (libsource (lib "eagle-import") (part "10MM"))
    )
    (comp (ref "D30")
      (value "10MM")
      (footprint "eagle-import:LED_10MM")
      (libsource (lib "eagle-import") (part "10MM"))
    )
    (comp (ref "D31")
      (value "10MM")
      (footprint "eagle-import:LED_10MM")
      (libsource (lib "eagle-import") (part "10MM"))
    )
    (comp (ref "D32")
      (value "10MM")
      (footprint "eagle-import:LED_10MM")
      (libsource (lib "eagle-import") (part "10MM"))
    )
    (comp (ref "D33")
      (value "10MM")
      (footprint "eagle-import:LED_10MM")
      (libsource (lib "eagle-import") (part "10MM"))
    )
    (comp (ref "D34")
      (value "10MM")
      (footprint "eagle-import:LED_10MM")
      (libsource (lib "eagle-import") (part "10MM"))
    )
    (comp (ref "D35")
      (value "10MM")
      (footprint "eagle-import:LED_10MM")
      (libsource (lib "eagle-import") (part "10MM"))
    )
    (comp (ref "D36")
      (value "10MM")
      (footprint "eagle-import:LED_10MM")
      (libsource (lib "eagle-import") (part "10MM"))
    )
    (comp (ref "D37")
      (value "10MM")
      (footprint "eagle-import:LED_10MM")
      (libsource (lib "eagle-import") (part "10MM"))
    )
    (comp (ref "D38")
      (value "10MM")
      (footprint "eagle-import:LED_10MM")
      (libsource (lib "eagle-import") (part "10MM"))
    )
    (comp (ref "D39")
      (value "10MM")
      (footprint "eagle-import:LED_10MM")
      (libsource (lib "eagle-import") (part "10MM"))
    )
    (comp (ref "D40")
      (value "10MM")
      (footprint "eagle-import:LED_10MM")
      (libsource (lib "eagle-import") (part "10MM"))
    )
    (comp (ref "D41")
      (value "10MM")
      (footprint "eagle-import:LED_10MM")
      (libsource (lib "eagle-import") (part "10MM"))
    )
    (comp (ref "D42")
      (value "10MM")
      (footprint "eagle-import:LED_10MM")
      (libsource (lib "eagle-import") (part "10MM"))
    )
    (comp (ref "D43")
      (value "10MM")
      (footprint "eagle-import:LED_10MM")
      (libsource (lib "eagle-import") (part "10MM"))
    )
    (comp (ref "D44")
      (value "10MM")
      (footprint "eagle-import:LED_10MM")
      (libsource (lib "eagle-import") (part "10MM"))
    )
    (comp (ref "D45")
      (value "10MM")
      (footprint "eagle-import:LED_10MM")
      (libsource (lib "eagle-import") (part "10MM"))
    )
    (comp (ref "D46")
      (value "10MM")
      (footprint "eagle-import:LED_10MM")
      (libsource (lib "eagle-import") (part "10MM"))
    )
    (comp (ref "D47")
      (value "10MM")
      (footprint "eagle-import:LED_10MM")
      (libsource (lib "eagle-import") (part "10MM"))
    )
    (comp (ref "D48")
      (value "10MM")
      (footprint "eagle-import:LED_10MM")
      (libsource (lib "eagle-import") (part "10MM"))
    )
    (comp (ref "D49")
      (value "10MM")
      (footprint "eagle-import:LED_10MM")
      (libsource (lib "eagle-import") (part "10MM"))
    )
    (comp (ref "D50")
      (value "10MM")
      (footprint "eagle-import:LED_10MM")
      (libsource (lib "eagle-import") (part "10MM"))
    )
    (comp (ref "D51")
      (value "10MM")
      (footprint "eagle-import:LED_10MM")
      (libsource (lib "eagle-import") (part "10MM"))
    )
    (comp (ref "D52")
      (value "10MM")
      (footprint "eagle-import:LED_10MM")
      (libsource (lib "eagle-import") (part "10MM"))
    )
    (comp (ref "D53")
      (value "10MM")
      (footprint "eagle-import:LED_10MM")
      (libsource (lib "eagle-import") (part "10MM"))
    )
    (comp (ref "D54")
      (value "10MM")
      (footprint "eagle-import:LED_10MM")
      (libsource (lib "eagle-import") (part "10MM"))
    )
    (comp (ref "D55")
      (value "10MM")
      (footprint "eagle-import:LED_10MM")
      (libsource (lib "eagle-import") (part "10MM"))
    )
    (comp (ref "D56")
      (value "10MM")
      (footprint "eagle-import:LED_10MM")
      (libsource (lib "eagle-import") (part "10MM"))
    )
    (comp (ref "D57")
      (value "10MM")
      (footprint "eagle-import:LED_10MM")
      (libsource (lib "eagle-import") (part "10MM"))
    )
    (comp (ref "D58")
      (value "10MM")
      (footprint "eagle-import:LED_10MM")
      (libsource (lib "eagle-import") (part "10MM"))
    )
    (comp (ref "D59")
      (value "10MM")
      (footprint "eagle-import:LED_10MM")
      (libsource (lib "eagle-import") (part "10MM"))
    )
    (comp (ref "D60")
      (value "10MM")
      (footprint "eagle-import:LED_10MM")
      (libsource (lib "eagle-import") (part "10MM"))
    )
    (comp (ref "D61")
      (value "10MM")
      (footprint "eagle-import:LED_10MM")
      (libsource (lib "eagle-import") (part "10MM"))
    )
    (comp (ref "D62")
      (value "10MM")
      (footprint "eagle-import:LED_10MM")
      (libsource (lib "eagle-import") (part "10MM"))
    )
    (comp (ref "D63")
      (value "10MM")
      (footprint "eagle-import:LED_10MM")
      (libsource (lib "eagle-import") (part "10MM"))
    )
    (comp (ref "D64")
      (value "10MM")
      (footprint "eagle-import:LED_10MM")
      (libsource (lib "eagle-import") (part "10MM"))
    )
    (comp (ref "D65")
      (value "10MM")
      (footprint "eagle-import:LED_10MM")
      (libsource (lib "eagle-import") (part "10MM"))
    )
    (comp (ref "D66")
      (value "10MM")
      (footprint "eagle-import:LED_10MM")
      (libsource (lib "eagle-import") (part "10MM"))
    )
    (comp (ref "D67")
      (value "10MM")
      (footprint "eagle-import:LED_10MM")
      (libsource (lib "eagle-import") (part "10MM"))
    )
    (comp (ref "D68")
      (value "10MM")
      (footprint "eagle-import:LED_10MM")
      (libsource (lib "eagle-import") (part "10MM"))
    )
    (comp (ref "D69")
      (value "10MM")
      (footprint "eagle-import:LED_10MM")
      (libsource (lib "eagle-import") (part "10MM"))
    )
    (comp (ref "D70")
      (value "10MM")
      (footprint "eagle-import:LED_10MM")
      (libsource (lib "eagle-import") (part "10MM"))
    )
    (comp (ref "D71")
      (value "10MM")
      (footprint "eagle-import:LED_10MM")
      (libsource (lib "eagle-import") (part "10MM"))
    )
    (comp (ref "D72")
      (value "10MM")
      (footprint "eagle-import:LED_10MM")
      (libsource (lib "eagle-import") (part "10MM"))
    )
    (comp (ref "D73")
      (value "10MM")
      (footprint "eagle-import:LED_10MM")
      (libsource (lib "eagle-import") (part "10MM"))
    )
    (comp (ref "D74")
      (value "10MM")
      (footprint "eagle-import:LED_10MM")
      (libsource (lib "eagle-import") (part "10MM"))
    )
    (comp (ref "D75")
      (value "10MM")
      (footprint "eagle-import:LED_10MM")
      (libsource (lib "eagle-import") (part "10MM"))
    )
    (comp (ref "D76")
      (value "10MM")
      (footprint "eagle-import:LED_10MM")
      (libsource (lib "eagle-import") (part "10MM"))
    )
    (comp (ref "D77")
      (value "10MM")
      (footprint "eagle-import:LED_10MM")
      (libsource (lib "eagle-import") (part "10MM"))
    )
    (comp (ref "D78")
      (value "10MM")
      (footprint "eagle-import:LED_10MM")
      (libsource (lib "eagle-import") (part "10MM"))
    )
    (comp (ref "D79")
      (value "10MM")
      (footprint "eagle-import:LED_10MM")
      (libsource (lib "eagle-import") (part "10MM"))
    )
    (comp (ref "D80")
      (value "10MM")
      (footprint "eagle-import:LED_10MM")
      (libsource (lib "eagle-import") (part "10MM"))
    )
    (comp (ref "D81")
      (value "10MM")
      (footprint "eagle-import:LED_10MM")
      (libsource (lib "eagle-import") (part "10MM"))
    )
    (comp (ref "D82")
      (value "10MM")
      (footprint "eagle-import:LED_10MM")
      (libsource (lib "eagle-import") (part "10MM"))
    )
    (comp (ref "D83")
      (value "10MM")
      (footprint "eagle-import:LED_10MM")
      (libsource (lib "eagle-import") (part "10MM"))
    )
    (comp (ref "D84")
      (value "10MM")
      (footprint "eagle-import:LED_10MM")
      (libsource (lib "eagle-import") (part "10MM"))
    )
    (comp (ref "D85")
      (value "10MM")
      (footprint "eagle-import:LED_10MM")
      (libsource (lib "eagle-import") (part "10MM"))
    )
    (comp (ref "D86")
      (value "10MM")
      (footprint "eagle-import:LED_10MM")
      (libsource (lib "eagle-import") (part "10MM"))
    )
    (comp (ref "D87")
      (value "10MM")
      (footprint "eagle-import:LED_10MM")
      (libsource (lib "eagle-import") (part "10MM"))
    )
    (comp (ref "D88")
      (value "10MM")
      (footprint "eagle-import:LED_10MM")
      (libsource (lib "eagle-import") (part "10MM"))
    )
    (comp (ref "D89")
      (value "10MM")
      (footprint "eagle-import:LED_10MM")
      (libsource (lib "eagle-import") (part "10MM"))
    )
    (comp (ref "D90")
      (value "10MM")
      (footprint "eagle-import:LED_10MM")
      (libsource (lib "eagle-import") (part "10MM"))
    )
    (comp (ref "D91")
      (value "10MM")
      (footprint "eagle-import:LED_10MM")
      (libsource (lib "eagle-import") (part "10MM"))
    )
    (comp (ref "D92")
      (value "10MM")
      (footprint "eagle-import:LED_10MM")
      (libsource (lib "eagle-import") (part "10MM"))
    )
    (comp (ref "D93")
      (value "10MM")
      (footprint "eagle-import:LED_10MM")
      (libsource (lib "eagle-import") (part "10MM"))
    )
    (comp (ref "D94")
      (value "10MM")
      (footprint "eagle-import:LED_10MM")
      (libsource (lib "eagle-import") (part "10MM"))
    )
    (comp (ref "D95")
      (value "10MM")
      (footprint "eagle-import:LED_10MM")
      (libsource (lib "eagle-import") (part "10MM"))
    )
    (comp (ref "D96")
      (value "10MM")
      (footprint "eagle-import:LED_10MM")
      (libsource (lib "eagle-import") (part "10MM"))
    )
    (comp (ref "D97")
      (value "10MM")
      (footprint "eagle-import:LED_10MM")
      (libsource (lib "eagle-import") (part "10MM"))
    )
    (comp (ref "D98")
      (value "10MM")
      (footprint "eagle-import:LED_10MM")
      (libsource (lib "eagle-import") (part "10MM"))
    )
    (comp (ref "D99")
      (value "10MM")
      (footprint "eagle-import:LED_10MM")
      (libsource (lib "eagle-import") (part "10MM"))
    )
    (comp (ref "D100")
      (value "10MM")
      (footprint "eagle-import:LED_10MM")
      (libsource (lib "eagle-import") (part "10MM"))
    )
    (comp (ref "D101")
      (value "10MM")
      (footprint "eagle-import:LED_10MM")
      (libsource (lib "eagle-import") (part "10MM"))
    )
    (comp (ref "D102")
      (value "10MM")
      (footprint "eagle-import:LED_10MM")
      (libsource (lib "eagle-import") (part "10MM"))
    )
    (comp (ref "D103")
      (value "10MM")
      (footprint "eagle-import:LED_10MM")
      (libsource (lib "eagle-import") (part "10MM"))
    )
    (comp (ref "D104")
      (value "10MM")
      (footprint "eagle-import:LED_10MM")
      (libsource (lib "eagle-import") (part "10MM"))
    )
    (comp (ref "D105")
      (value "10MM")
      (footprint "eagle-import:LED_10MM")
      (libsource (lib "eagle-import") (part "10MM"))
    )
    (comp (ref "D106")
      (value "10MM")
      (footprint "eagle-import:LED_10MM")
      (libsource (lib "eagle-import") (part "10MM"))
    )
    (comp (ref "D107")
      (value "10MM")
      (footprint "eagle-import:LED_10MM")
      (libsource (lib "eagle-import") (part "10MM"))
    )
    (comp (ref "D108")
      (value "10MM")
      (footprint "eagle-import:LED_10MM")
      (libsource (lib "eagle-import") (part "10MM"))
    )
    (comp (ref "D109")
      (value "10MM")
      (footprint "eagle-import:LED_10MM")
      (libsource (lib "eagle-import") (part "10MM"))
    )
    (comp (ref "D110")
      (value "10MM")
      (footprint "eagle-import:LED_10MM")
      (libsource (lib "eagle-import") (part "10MM"))
    )
    (comp (ref "D111")
      (value "10MM")
      (footprint "eagle-import:LED_10MM")
      (libsource (lib "eagle-import") (part "10MM"))
    )
    (comp (ref "D112")
      (value "10MM")
      (footprint "eagle-import:LED_10MM")
      (libsource (lib "eagle-import") (part "10MM"))
    )
    (comp (ref "D113")
      (value "10MM")
      (footprint "eagle-import:LED_10MM")
      (libsource (lib "eagle-import") (part "10MM"))
    )
    (comp (ref "D114")
      (value "10MM")
      (footprint "eagle-import:LED_10MM")
      (libsource (lib "eagle-import") (part "10MM"))
    )
    (comp (ref "D115")
      (value "10MM")
      (footprint "eagle-import:LED_10MM")
      (libsource (lib "eagle-import") (part "10MM"))
    )
    (comp (ref "D116")
      (value "10MM")
      (footprint "eagle-import:LED_10MM")
      (libsource (lib "eagle-import") (part "10MM"))
    )
    (comp (ref "D117")
      (value "10MM")
      (footprint "eagle-import:LED_10MM")
      (libsource (lib "eagle-import") (part "10MM"))
    )
    (comp (ref "D118")
      (value "10MM")
      (footprint "eagle-import:LED_10MM")
      (libsource (lib "eagle-import") (part "10MM"))
    )
    (comp (ref "D119")
      (value "10MM")
      (footprint "eagle-import:LED_10MM")
      (libsource (lib "eagle-import") (part "10MM"))
    )
    (comp (ref "D120")
      (value "10MM")
      (footprint "eagle-import:LED_10MM")
      (libsource (lib "eagle-import") (part "10MM"))
    )
    (comp (ref "D121")
      (value "10MM")
      (footprint "eagle-import:LED_10MM")
      (libsource (lib "eagle-import") (part "10MM"))
    )
    (comp (ref "D122")
      (value "10MM")
      (footprint "eagle-import:LED_10MM")
      (libsource (lib "eagle-import") (part "10MM"))
    )
    (comp (ref "D123")
      (value "10MM")
      (footprint "eagle-import:LED_10MM")
      (libsource (lib "eagle-import") (part "10MM"))
    )
    (comp (ref "D124")
      (value "10MM")
      (footprint "eagle-import:LED_10MM")
      (libsource (lib "eagle-import") (part "10MM"))
    )
    (comp (ref "D125")
      (value "10MM")
      (footprint "eagle-import:LED_10MM")
      (libsource (lib "eagle-import") (part "10MM"))
    )
    (comp (ref "D126")
      (value "10MM")
      (footprint "eagle-import:LED_10MM")
      (libsource (lib "eagle-import") (part "10MM"))
    )
    (comp (ref "D127")
      (value "10MM")
      (footprint "eagle-import:LED_10MM")
      (libsource (lib "eagle-import") (part "10MM"))
    )
    (comp (ref "D128")
      (value "10MM")
      (footprint "eagle-import:LED_10MM")
      (libsource (lib "eagle-import") (part "10MM"))
    )
    (comp (ref "D129")
      (value "10MM")
      (footprint "eagle-import:LED_10MM")
      (libsource (lib "eagle-import") (part "10MM"))
    )
    (comp (ref "D130")
      (value "10MM")
      (footprint "eagle-import:LED_10MM")
      (libsource (lib "eagle-import") (part "10MM"))
    )
    (comp (ref "D131")
      (value "10MM")
      (footprint "eagle-import:LED_10MM")
      (libsource (lib "eagle-import") (part "10MM"))
    )
    (comp (ref "D132")
      (value "10MM")
      (footprint "eagle-import:LED_10MM")
      (libsource (lib "eagle-import") (part "10MM"))
    )
    (comp (ref "D133")
      (value "10MM")
      (footprint "eagle-import:LED_10MM")
      (libsource (lib "eagle-import") (part "10MM"))
    )
    (comp (ref "D134")
      (value "10MM")
      (footprint "eagle-import:LED_10MM")
      (libsource (lib "eagle-import") (part "10MM"))
    )
    (comp (ref "D135")
      (value "10MM")
      (footprint "eagle-import:LED_10MM")
      (libsource (lib "eagle-import") (part "10MM"))
    )
    (comp (ref "D136")
      (value "10MM")
      (footprint "eagle-import:LED_10MM")
      (libsource (lib "eagle-import") (part "10MM"))
    )
    (comp (ref "D137")
      (value "10MM")
      (footprint "eagle-import:LED_10MM")
      (libsource (lib "eagle-import") (part "10MM"))
    )
    (comp (ref "D138")
      (value "10MM")
      (footprint "eagle-import:LED_10MM")
      (libsource (lib "eagle-import") (part "10MM"))
    )
    (comp (ref "D139")
      (value "10MM")
      (footprint "eagle-import:LED_10MM")
      (libsource (lib "eagle-import") (part "10MM"))
    )
    (comp (ref "D140")
      (value "10MM")
      (footprint "eagle-import:LED_10MM")
      (libsource (lib "eagle-import") (part "10MM"))
    )
    (comp (ref "IC5")
      (value "74LS595D")
      (footprint "eagle-import:SO16")
      (libsource (lib "eagle-import") (part "74595DLS"))
    )
    (comp (ref "IC6")
      (value "74LS595D")
      (footprint "eagle-import:SO16")
      (libsource (lib "eagle-import") (part "74595DLS"))
    )
    (comp (ref "IC7")
      (value "74LS595D")
      (footprint "eagle-import:SO16")
      (libsource (lib "eagle-import") (part "74595DLS"))
    )
    (comp (ref "IC8")
      (value "74LS595D")
      (footprint "eagle-import:SO16")
      (libsource (lib "eagle-import") (part "74595DLS"))
    )
    (comp (ref "JP3")
      (value "PINHD-2X5")
      (footprint "eagle-import:2X05")
      (libsource (lib "eagle-import") (part "PINHD-2X5"))
    )
    (comp (ref "C5")
      (value "0.1UF")
      (footprint "eagle-import:C0603")
      (libsource (lib "eagle-import") (part "C-USC0603"))
    )
    (comp (ref "C6")
      (value "1UF")
      (footprint "eagle-import:C0603")
      (libsource (lib "eagle-import") (part "C-USC0603"))
    )
    (comp (ref "C7")
      (value "1UF")
      (footprint "eagle-import:C0603")
      (libsource (lib "eagle-import") (part "C-USC0603"))
    )
    (comp (ref "D141")
      (value "10MM")
      (footprint "eagle-import:LED_10MM")
      (libsource (lib "eagle-import") (part "10MM"))
    )
    (comp (ref "D142")
      (value "10MM")
      (footprint "eagle-import:LED_10MM")
      (libsource (lib "eagle-import") (part "10MM"))
    )
    (comp (ref "D143")
      (value "10MM")
      (footprint "eagle-import:LED_10MM")
      (libsource (lib "eagle-import") (part "10MM"))
    )
    (comp (ref "D144")
      (value "10MM")
      (footprint "eagle-import:LED_10MM")
      (libsource (lib "eagle-import") (part "10MM"))
    )
    (comp (ref "D145")
      (value "10MM")
      (footprint "eagle-import:LED_10MM")
      (libsource (lib "eagle-import") (part "10MM"))
    )
    (comp (ref "D146")
      (value "10MM")
      (footprint "eagle-import:LED_10MM")
      (libsource (lib "eagle-import") (part "10MM"))
    )
    (comp (ref "D147")
      (value "10MM")
      (footprint "eagle-import:LED_10MM")
      (libsource (lib "eagle-import") (part "10MM"))
    )
    (comp (ref "D148")
      (value "10MM")
      (footprint "eagle-import:LED_10MM")
      (libsource (lib "eagle-import") (part "10MM"))
    )
    (comp (ref "D149")
      (value "10MM")
      (footprint "eagle-import:LED_10MM")
      (libsource (lib "eagle-import") (part "10MM"))
    )
    (comp (ref "D150")
      (value "10MM")
      (footprint "eagle-import:LED_10MM")
      (libsource (lib "eagle-import") (part "10MM"))
    )
    (comp (ref "D151")
      (value "10MM")
      (footprint "eagle-import:LED_10MM")
      (libsource (lib "eagle-import") (part "10MM"))
    )
    (comp (ref "D152")
      (value "10MM")
      (footprint "eagle-import:LED_10MM")
      (libsource (lib "eagle-import") (part "10MM"))
    )
    (comp (ref "D153")
      (value "10MM")
      (footprint "eagle-import:LED_10MM")
      (libsource (lib "eagle-import") (part "10MM"))
    )
    (comp (ref "D154")
      (value "10MM")
      (footprint "eagle-import:LED_10MM")
      (libsource (lib "eagle-import") (part "10MM"))
    )
    (comp (ref "D155")
      (value "10MM")
      (footprint "eagle-import:LED_10MM")
      (libsource (lib "eagle-import") (part "10MM"))
    )
    (comp (ref "D156")
      (value "10MM")
      (footprint "eagle-import:LED_10MM")
      (libsource (lib "eagle-import") (part "10MM"))
    )
    (comp (ref "D157")
      (value "10MM")
      (footprint "eagle-import:LED_10MM")
      (libsource (lib "eagle-import") (part "10MM"))
    )
    (comp (ref "D158")
      (value "10MM")
      (footprint "eagle-import:LED_10MM")
      (libsource (lib "eagle-import") (part "10MM"))
    )
    (comp (ref "D159")
      (value "10MM")
      (footprint "eagle-import:LED_10MM")
      (libsource (lib "eagle-import") (part "10MM"))
    )
    (comp (ref "D160")
      (value "10MM")
      (footprint "eagle-import:LED_10MM")
      (libsource (lib "eagle-import") (part "10MM"))
    )
    (comp (ref "D161")
      (value "10MM")
      (footprint "eagle-import:LED_10MM")
      (libsource (lib "eagle-import") (part "10MM"))
    )
    (comp (ref "D162")
      (value "10MM")
      (footprint "eagle-import:LED_10MM")
      (libsource (lib "eagle-import") (part "10MM"))
    )
    (comp (ref "D163")
      (value "10MM")
      (footprint "eagle-import:LED_10MM")
      (libsource (lib "eagle-import") (part "10MM"))
    )
    (comp (ref "D164")
      (value "10MM")
      (footprint "eagle-import:LED_10MM")
      (libsource (lib "eagle-import") (part "10MM"))
    )
    (comp (ref "D165")
      (value "10MM")
      (footprint "eagle-import:LED_10MM")
      (libsource (lib "eagle-import") (part "10MM"))
    )
    (comp (ref "D166")
      (value "10MM")
      (footprint "eagle-import:LED_10MM")
      (libsource (lib "eagle-import") (part "10MM"))
    )
    (comp (ref "D167")
      (value "10MM")
      (footprint "eagle-import:LED_10MM")
      (libsource (lib "eagle-import") (part "10MM"))
    )
    (comp (ref "D168")
      (value "10MM")
      (footprint "eagle-import:LED_10MM")
      (libsource (lib "eagle-import") (part "10MM"))
    )
    (comp (ref "D169")
      (value "10MM")
      (footprint "eagle-import:LED_10MM")
      (libsource (lib "eagle-import") (part "10MM"))
    )
    (comp (ref "D170")
      (value "10MM")
      (footprint "eagle-import:LED_10MM")
      (libsource (lib "eagle-import") (part "10MM"))
    )
    (comp (ref "D171")
      (value "10MM")
      (footprint "eagle-import:LED_10MM")
      (libsource (lib "eagle-import") (part "10MM"))
    )
    (comp (ref "D172")
      (value "10MM")
      (footprint "eagle-import:LED_10MM")
      (libsource (lib "eagle-import") (part "10MM"))
    )
    (comp (ref "D173")
      (value "10MM")
      (footprint "eagle-import:LED_10MM")
      (libsource (lib "eagle-import") (part "10MM"))
    )
    (comp (ref "D174")
      (value "10MM")
      (footprint "eagle-import:LED_10MM")
      (libsource (lib "eagle-import") (part "10MM"))
    )
    (comp (ref "D175")
      (value "10MM")
      (footprint "eagle-import:LED_10MM")
      (libsource (lib "eagle-import") (part "10MM"))
    )
    (comp (ref "JP2")
      (value "PINHD-2X5")
      (footprint "eagle-import:2X05")
      (libsource (lib "eagle-import") (part "PINHD-2X5"))
    )
    (comp (ref "P1")
      (value "THROUGH_HOLE18AWG")
      (footprint "eagle-import:18AWG_TH")
      (libsource (lib "eagle-import") (part "THROUGH_HOLE18AWG"))
    )
    (comp (ref "P2")
      (value "THROUGH_HOLE18AWG")
      (footprint "eagle-import:18AWG_TH")
      (libsource (lib "eagle-import") (part "THROUGH_HOLE18AWG"))
    )
    (comp (ref "P3")
      (value "THROUGH_HOLE18AWG")
      (footprint "eagle-import:18AWG_TH")
      (libsource (lib "eagle-import") (part "THROUGH_HOLE18AWG"))
    )
    (comp (ref "P4")
      (value "THROUGH_HOLE18AWG")
      (footprint "eagle-import:18AWG_TH")
      (libsource (lib "eagle-import") (part "THROUGH_HOLE18AWG"))
    )
    (comp (ref "Q28")
      (value "ZXMN6A11ZTA")
      (footprint "eagle-import:SOT89")
      (libsource (lib "eagle-import") (part "ZXMN6A11ZTA"))
    )
    (comp (ref "Q29")
      (value "ZXMN6A11ZTA")
      (footprint "eagle-import:SOT89")
      (libsource (lib "eagle-import") (part "ZXMN6A11ZTA"))
    )
    (comp (ref "Q30")
      (value "ZXMN6A11ZTA")
      (footprint "eagle-import:SOT89")
      (libsource (lib "eagle-import") (part "ZXMN6A11ZTA"))
    )
    (comp (ref "Q31")
      (value "ZXMN6A11ZTA")
      (footprint "eagle-import:SOT89")
      (libsource (lib "eagle-import") (part "ZXMN6A11ZTA"))
    )
    (comp (ref "Q32")
      (value "ZXMN6A11ZTA")
      (footprint "eagle-import:SOT89")
      (libsource (lib "eagle-import") (part "ZXMN6A11ZTA"))
    )
    (comp (ref "Q33")
      (value "ZXMN6A11ZTA")
      (footprint "eagle-import:SOT89")
      (libsource (lib "eagle-import") (part "ZXMN6A11ZTA"))
    )
    (comp (ref "Q34")
      (value "ZXMN6A11ZTA")
      (footprint "eagle-import:SOT89")
      (libsource (lib "eagle-import") (part "ZXMN6A11ZTA"))
    )
    (comp (ref "R26")
      (value "100")
      (footprint "eagle-import:R0603")
      (libsource (lib "eagle-import") (part "R-US_R0603"))
    )
    (comp (ref "R27")
      (value "100")
      (footprint "eagle-import:R0603")
      (libsource (lib "eagle-import") (part "R-US_R0603"))
    )
    (comp (ref "R28")
      (value "100")
      (footprint "eagle-import:R0603")
      (libsource (lib "eagle-import") (part "R-US_R0603"))
    )
    (comp (ref "R29")
      (value "100")
      (footprint "eagle-import:R0603")
      (libsource (lib "eagle-import") (part "R-US_R0603"))
    )
    (comp (ref "R30")
      (value "100")
      (footprint "eagle-import:R0603")
      (libsource (lib "eagle-import") (part "R-US_R0603"))
    )
    (comp (ref "R31")
      (value "100")
      (footprint "eagle-import:R0603")
      (libsource (lib "eagle-import") (part "R-US_R0603"))
    )
    (comp (ref "R32")
      (value "100")
      (footprint "eagle-import:R0603")
      (libsource (lib "eagle-import") (part "R-US_R0603"))
    )
    (comp (ref "R83")
      (value "10K")
      (footprint "eagle-import:R0603")
      (libsource (lib "eagle-import") (part "R-US_R0603"))
    )
    (comp (ref "R84")
      (value "10K")
      (footprint "eagle-import:R0603")
      (libsource (lib "eagle-import") (part "R-US_R0603"))
    )
    (comp (ref "R85")
      (value "10K")
      (footprint "eagle-import:R0603")
      (libsource (lib "eagle-import") (part "R-US_R0603"))
    )
    (comp (ref "R86")
      (value "10K")
      (footprint "eagle-import:R0603")
      (libsource (lib "eagle-import") (part "R-US_R0603"))
    )
    (comp (ref "R87")
      (value "10K")
      (footprint "eagle-import:R0603")
      (libsource (lib "eagle-import") (part "R-US_R0603"))
    )
    (comp (ref "R88")
      (value "10K")
      (footprint "eagle-import:R0603")
      (libsource (lib "eagle-import") (part "R-US_R0603"))
    )
    (comp (ref "R89")
      (value "10K")
      (footprint "eagle-import:R0603")
      (libsource (lib "eagle-import") (part "R-US_R0603"))
    )
    (comp (ref "R90")
      (value "NL")
      (footprint "eagle-import:R0603")
      (libsource (lib "eagle-import") (part "R-US_R0603"))
    )
    (comp (ref "R91")
      (value "NL")
      (footprint "eagle-import:R0603")
      (libsource (lib "eagle-import") (part "R-US_R0603"))
    )
    (comp (ref "R92")
      (value "NL")
      (footprint "eagle-import:R0603")
      (libsource (lib "eagle-import") (part "R-US_R0603"))
    )
    (comp (ref "R93")
      (value "1K")
      (footprint "eagle-import:R0603")
      (libsource (lib "eagle-import") (part "R-US_R0603"))
    )
    (comp (ref "R98")
      (value "NL")
      (footprint "eagle-import:R0603")
      (libsource (lib "eagle-import") (part "R-US_R0603"))
    )
    (comp (ref "R99")
      (value "NL")
      (footprint "eagle-import:R0603")
      (libsource (lib "eagle-import") (part "R-US_R0603"))
    )
    (comp (ref "U1")
      (value "TXB0104PW")
      (footprint "eagle-import:TSSOP14")
      (libsource (lib "eagle-import") (part "TXB0104PW"))
    )
    (comp (ref "U2")
      (value "MCP1703T-3302E/CB")
      (footprint "eagle-import:SOT23")
      (libsource (lib "eagle-import") (part "MCP1703/CBT-3302E"))
    )
  )
  (nets
    (net (code "1") (name "CLOCK") (class "Default")
      (node (ref "IC5") (pin "11") (pinfunction "SCK_11") (pintype "input"))
      (node (ref "IC6") (pin "11") (pinfunction "SCK_11") (pintype "input"))
      (node (ref "IC7") (pin "11") (pinfunction "SCK_11") (pintype "input"))
      (node (ref "IC8") (pin "11") (pinfunction "SCK_11") (pintype "input"))
      (node (ref "JP3") (pin "2") (pinfunction "2_2") (pintype "passive"))
      (node (ref "R91") (pin "2") (pinfunction "2_2") (pintype "passive"))
      (node (ref "U1") (pin "12") (pinfunction "B2_12") (pintype "bidirectional"))
    )
    (net (code "2") (name "CLOCK_A") (class "Default")
      (node (ref "JP2") (pin "2") (pinfunction "2_2") (pintype "passive"))
      (node (ref "R91") (pin "1") (pinfunction "1_1") (pintype "passive"))
      (node (ref "U1") (pin "3") (pinfunction "A2_3") (pintype "bidirectional"))
    )
    (net (code "3") (name "COL1") (class "Default")
      (node (ref "D1") (pin "A") (pinfunction "A_A") (pintype "passive"))
      (node (ref "D2") (pin "A") (pinfunction "A_A") (pintype "passive"))
      (node (ref "D3") (pin "A") (pinfunction "A_A") (pintype "passive"))
      (node (ref "D4") (pin "A") (pinfunction "A_A") (pintype "passive"))
      (node (ref "D5") (pin "A") (pinfunction "A_A") (pintype "passive"))
      (node (ref "D6") (pin "A") (pinfunction "A_A") (pintype "passive"))
      (node (ref "D7") (pin "A") (pinfunction "A_A") (pintype "passive"))
      (node (ref "R1") (pin "1") (pinfunction "1_1") (pintype "passive"))
    )
    (net (code "4") (name "COL1_DRV") (class "Default")
      (node (ref "IC5") (pin "7") (pinfunction "QH_7") (pintype "tri_state"))
      (node (ref "R33") (pin "1") (pinfunction "1_1") (pintype "passive"))
    )
    (net (code "5") (name "COL2") (class "Default")
      (node (ref "D10") (pin "A") (pinfunction "A_A") (pintype "passive"))
      (node (ref "D11") (pin "A") (pinfunction "A_A") (pintype "passive"))
      (node (ref "D12") (pin "A") (pinfunction "A_A") (pintype "passive"))
      (node (ref "D13") (pin "A") (pinfunction "A_A") (pintype "passive"))
      (node (ref "D14") (pin "A") (pinfunction "A_A") (pintype "passive"))
      (node (ref "D8") (pin "A") (pinfunction "A_A") (pintype "passive"))
      (node (ref "D9") (pin "A") (pinfunction "A_A") (pintype "passive"))
      (node (ref "R2") (pin "1") (pinfunction "1_1") (pintype "passive"))
    )
    (net (code "6") (name "COL2_DRV") (class "Default")
      (node (ref "IC6") (pin "15") (pinfunction "QA_15") (pintype "tri_state"))
      (node (ref "R34") (pin "1") (pinfunction "1_1") (pintype "passive"))
    )
    (net (code "7") (name "COL3") (class "Default")
      (node (ref "D15") (pin "A") (pinfunction "A_A") (pintype "passive"))
      (node (ref "D16") (pin "A") (pinfunction "A_A") (pintype "passive"))
      (node (ref "D17") (pin "A") (pinfunction "A_A") (pintype "passive"))
      (node (ref "D18") (pin "A") (pinfunction "A_A") (pintype "passive"))
      (node (ref "D19") (pin "A") (pinfunction "A_A") (pintype "passive"))
      (node (ref "D20") (pin "A") (pinfunction "A_A") (pintype "passive"))
      (node (ref "D21") (pin "A") (pinfunction "A_A") (pintype "passive"))
      (node (ref "R3") (pin "1") (pinfunction "1_1") (pintype "passive"))
    )
    (net (code "8") (name "COL3_DRV") (class "Default")
      (node (ref "IC6") (pin "1") (pinfunction "QB_1") (pintype "tri_state"))
      (node (ref "R35") (pin "1") (pinfunction "1_1") (pintype "passive"))
    )
    (net (code "9") (name "COL4") (class "Default")
      (node (ref "D22") (pin "A") (pinfunction "A_A") (pintype "passive"))
      (node (ref "D23") (pin "A") (pinfunction "A_A") (pintype "passive"))
      (node (ref "D24") (pin "A") (pinfunction "A_A") (pintype "passive"))
      (node (ref "D25") (pin "A") (pinfunction "A_A") (pintype "passive"))
      (node (ref "D26") (pin "A") (pinfunction "A_A") (pintype "passive"))
      (node (ref "D27") (pin "A") (pinfunction "A_A") (pintype "passive"))
      (node (ref "D28") (pin "A") (pinfunction "A_A") (pintype "passive"))
      (node (ref "R4") (pin "1") (pinfunction "1_1") (pintype "passive"))
    )
    (net (code "10") (name "COL4_DRV") (class "Default")
      (node (ref "IC6") (pin "2") (pinfunction "QC_2") (pintype "tri_state"))
      (node (ref "R36") (pin "1") (pinfunction "1_1") (pintype "passive"))
    )
    (net (code "11") (name "COL5") (class "Default")
      (node (ref "D29") (pin "A") (pinfunction "A_A") (pintype "passive"))
      (node (ref "D30") (pin "A") (pinfunction "A_A") (pintype "passive"))
      (node (ref "D31") (pin "A") (pinfunction "A_A") (pintype "passive"))
      (node (ref "D32") (pin "A") (pinfunction "A_A") (pintype "passive"))
      (node (ref "D33") (pin "A") (pinfunction "A_A") (pintype "passive"))
      (node (ref "D34") (pin "A") (pinfunction "A_A") (pintype "passive"))
      (node (ref "D35") (pin "A") (pinfunction "A_A") (pintype "passive"))
      (node (ref "R5") (pin "1") (pinfunction "1_1") (pintype "passive"))
    )
    (net (code "12") (name "COL5_DRV") (class "Default")
      (node (ref "IC6") (pin "3") (pinfunction "QD_3") (pintype "tri_state"))
      (node (ref "R37") (pin "1") (pinfunction "1_1") (pintype "passive"))
    )
    (net (code "13") (name "COL6") (class "Default")
      (node (ref "D36") (pin "A") (pinfunction "A_A") (pintype "passive"))
      (node (ref "D37") (pin "A") (pinfunction "A_A") (pintype "passive"))
      (node (ref "D38") (pin "A") (pinfunction "A_A") (pintype "passive"))
      (node (ref "D39") (pin "A") (pinfunction "A_A") (pintype "passive"))
      (node (ref "D40") (pin "A") (pinfunction "A_A") (pintype "passive"))
      (node (ref "D41") (pin "A") (pinfunction "A_A") (pintype "passive"))
      (node (ref "D42") (pin "A") (pinfunction "A_A") (pintype "passive"))
      (node (ref "R6") (pin "1") (pinfunction "1_1") (pintype "passive"))
    )
    (net (code "14") (name "COL6_DRV") (class "Default")
      (node (ref "IC6") (pin "4") (pinfunction "QE_4") (pintype "tri_state"))
      (node (ref "R38") (pin "1") (pinfunction "1_1") (pintype "passive"))
    )
    (net (code "15") (name "COL7") (class "Default")
      (node (ref "D43") (pin "A") (pinfunction "A_A") (pintype "passive"))
      (node (ref "D44") (pin "A") (pinfunction "A_A") (pintype "passive"))
      (node (ref "D45") (pin "A") (pinfunction "A_A") (pintype "passive"))
      (node (ref "D46") (pin "A") (pinfunction "A_A") (pintype "passive"))
      (node (ref "D47") (pin "A") (pinfunction "A_A") (pintype "passive"))
      (node (ref "D48") (pin "A") (pinfunction "A_A") (pintype "passive"))
      (node (ref "D49") (pin "A") (pinfunction "A_A") (pintype "passive"))
      (node (ref "R7") (pin "1") (pinfunction "1_1") (pintype "passive"))
    )
    (net (code "16") (name "COL7_DRV") (class "Default")
      (node (ref "IC6") (pin "5") (pinfunction "QF_5") (pintype "tri_state"))
      (node (ref "R39") (pin "1") (pinfunction "1_1") (pintype "passive"))
    )
    (net (code "17") (name "COL8") (class "Default")
      (node (ref "D50") (pin "A") (pinfunction "A_A") (pintype "passive"))
      (node (ref "D51") (pin "A") (pinfunction "A_A") (pintype "passive"))
      (node (ref "D52") (pin "A") (pinfunction "A_A") (pintype "passive"))
      (node (ref "D53") (pin "A") (pinfunction "A_A") (pintype "passive"))
      (node (ref "D54") (pin "A") (pinfunction "A_A") (pintype "passive"))
      (node (ref "D55") (pin "A") (pinfunction "A_A") (pintype "passive"))
      (node (ref "D56") (pin "A") (pinfunction "A_A") (pintype "passive"))
      (node (ref "R8") (pin "1") (pinfunction "1_1") (pintype "passive"))
    )
    (net (code "18") (name "COL8_DRV") (class "Default")
      (node (ref "IC6") (pin "6") (pinfunction "QG_6") (pintype "tri_state"))
      (node (ref "R40") (pin "1") (pinfunction "1_1") (pintype "passive"))
    )
    (net (code "19") (name "COL9") (class "Default")
      (node (ref "D57") (pin "A") (pinfunction "A_A") (pintype "passive"))
      (node (ref "D58") (pin "A") (pinfunction "A_A") (pintype "passive"))
      (node (ref "D59") (pin "A") (pinfunction "A_A") (pintype "passive"))
      (node (ref "D60") (pin "A") (pinfunction "A_A") (pintype "passive"))
      (node (ref "D61") (pin "A") (pinfunction "A_A") (pintype "passive"))
      (node (ref "D62") (pin "A") (pinfunction "A_A") (pintype "passive"))
      (node (ref "D63") (pin "A") (pinfunction "A_A") (pintype "passive"))
      (node (ref "R9") (pin "1") (pinfunction "1_1") (pintype "passive"))
    )
    (net (code "20") (name "COL9_DRV") (class "Default")
      (node (ref "IC6") (pin "7") (pinfunction "QH_7") (pintype "tri_state"))
      (node (ref "R41") (pin "1") (pinfunction "1_1") (pintype "passive"))
    )
    (net (code "21") (name "COL10") (class "Default")
      (node (ref "D64") (pin "A") (pinfunction "A_A") (pintype "passive"))
      (node (ref "D65") (pin "A") (pinfunction "A_A") (pintype "passive"))
      (node (ref "D66") (pin "A") (pinfunction "A_A") (pintype "passive"))
      (node (ref "D67") (pin "A") (pinfunction "A_A") (pintype "passive"))
      (node (ref "D68") (pin "A") (pinfunction "A_A") (pintype "passive"))
      (node (ref "D69") (pin "A") (pinfunction "A_A") (pintype "passive"))
      (node (ref "D70") (pin "A") (pinfunction "A_A") (pintype "passive"))
      (node (ref "R10") (pin "1") (pinfunction "1_1") (pintype "passive"))
    )
    (net (code "22") (name "COL10_DRV") (class "Default")
      (node (ref "IC7") (pin "15") (pinfunction "QA_15") (pintype "tri_state"))
      (node (ref "R42") (pin "1") (pinfunction "1_1") (pintype "passive"))
    )
    (net (code "23") (name "COL11") (class "Default")
      (node (ref "D71") (pin "A") (pinfunction "A_A") (pintype "passive"))
      (node (ref "D72") (pin "A") (pinfunction "A_A") (pintype "passive"))
      (node (ref "D73") (pin "A") (pinfunction "A_A") (pintype "passive"))
      (node (ref "D74") (pin "A") (pinfunction "A_A") (pintype "passive"))
      (node (ref "D75") (pin "A") (pinfunction "A_A") (pintype "passive"))
      (node (ref "D76") (pin "A") (pinfunction "A_A") (pintype "passive"))
      (node (ref "D77") (pin "A") (pinfunction "A_A") (pintype "passive"))
      (node (ref "R43") (pin "1") (pinfunction "1_1") (pintype "passive"))
    )
    (net (code "24") (name "COL11_DRV") (class "Default")
      (node (ref "IC7") (pin "1") (pinfunction "QB_1") (pintype "tri_state"))
      (node (ref "R11") (pin "1") (pinfunction "1_1") (pintype "passive"))
    )
    (net (code "25") (name "COL12") (class "Default")
      (node (ref "D78") (pin "A") (pinfunction "A_A") (pintype "passive"))
      (node (ref "D79") (pin "A") (pinfunction "A_A") (pintype "passive"))
      (node (ref "D80") (pin "A") (pinfunction "A_A") (pintype "passive"))
      (node (ref "D81") (pin "A") (pinfunction "A_A") (pintype "passive"))
      (node (ref "D82") (pin "A") (pinfunction "A_A") (pintype "passive"))
      (node (ref "D83") (pin "A") (pinfunction "A_A") (pintype "passive"))
      (node (ref "D84") (pin "A") (pinfunction "A_A") (pintype "passive"))
      (node (ref "R44") (pin "1") (pinfunction "1_1") (pintype "passive"))
    )
    (net (code "26") (name "COL12_DRV") (class "Default")
      (node (ref "IC7") (pin "2") (pinfunction "QC_2") (pintype "tri_state"))
      (node (ref "R12") (pin "1") (pinfunction "1_1") (pintype "passive"))
    )
    (net (code "27") (name "COL13") (class "Default")
      (node (ref "D85") (pin "A") (pinfunction "A_A") (pintype "passive"))
      (node (ref "D86") (pin "A") (pinfunction "A_A") (pintype "passive"))
      (node (ref "D87") (pin "A") (pinfunction "A_A") (pintype "passive"))
      (node (ref "D88") (pin "A") (pinfunction "A_A") (pintype "passive"))
      (node (ref "D89") (pin "A") (pinfunction "A_A") (pintype "passive"))
      (node (ref "D90") (pin "A") (pinfunction "A_A") (pintype "passive"))
      (node (ref "D91") (pin "A") (pinfunction "A_A") (pintype "passive"))
      (node (ref "R45") (pin "1") (pinfunction "1_1") (pintype "passive"))
    )
    (net (code "28") (name "COL13_DRV") (class "Default")
      (node (ref "IC7") (pin "3") (pinfunction "QD_3") (pintype "tri_state"))
      (node (ref "R13") (pin "1") (pinfunction "1_1") (pintype "passive"))
    )
    (net (code "29") (name "COL14") (class "Default")
      (node (ref "D92") (pin "A") (pinfunction "A_A") (pintype "passive"))
      (node (ref "D93") (pin "A") (pinfunction "A_A") (pintype "passive"))
      (node (ref "D94") (pin "A") (pinfunction "A_A") (pintype "passive"))
      (node (ref "D95") (pin "A") (pinfunction "A_A") (pintype "passive"))
      (node (ref "D96") (pin "A") (pinfunction "A_A") (pintype "passive"))
      (node (ref "D97") (pin "A") (pinfunction "A_A") (pintype "passive"))
      (node (ref "D98") (pin "A") (pinfunction "A_A") (pintype "passive"))
      (node (ref "R46") (pin "1") (pinfunction "1_1") (pintype "passive"))
    )
    (net (code "30") (name "COL14_DRV") (class "Default")
      (node (ref "IC7") (pin "4") (pinfunction "QE_4") (pintype "tri_state"))
      (node (ref "R14") (pin "1") (pinfunction "1_1") (pintype "passive"))
    )
    (net (code "31") (name "COL15") (class "Default")
      (node (ref "D100") (pin "A") (pinfunction "A_A") (pintype "passive"))
      (node (ref "D101") (pin "A") (pinfunction "A_A") (pintype "passive"))
      (node (ref "D102") (pin "A") (pinfunction "A_A") (pintype "passive"))
      (node (ref "D103") (pin "A") (pinfunction "A_A") (pintype "passive"))
      (node (ref "D104") (pin "A") (pinfunction "A_A") (pintype "passive"))
      (node (ref "D105") (pin "A") (pinfunction "A_A") (pintype "passive"))
      (node (ref "D99") (pin "A") (pinfunction "A_A") (pintype "passive"))
      (node (ref "R47") (pin "1") (pinfunction "1_1") (pintype "passive"))
    )
    (net (code "32") (name "COL15_DRV") (class "Default")
      (node (ref "IC7") (pin "5") (pinfunction "QF_5") (pintype "tri_state"))
      (node (ref "R15") (pin "1") (pinfunction "1_1") (pintype "passive"))
    )
    (net (code "33") (name "COL16") (class "Default")
      (node (ref "D106") (pin "A") (pinfunction "A_A") (pintype "passive"))
      (node (ref "D107") (pin "A") (pinfunction "A_A") (pintype "passive"))
      (node (ref "D108") (pin "A") (pinfunction "A_A") (pintype "passive"))
      (node (ref "D109") (pin "A") (pinfunction "A_A") (pintype "passive"))
      (node (ref "D110") (pin "A") (pinfunction "A_A") (pintype "passive"))
      (node (ref "D111") (pin "A") (pinfunction "A_A") (pintype "passive"))
      (node (ref "D112") (pin "A") (pinfunction "A_A") (pintype "passive"))
      (node (ref "R48") (pin "1") (pinfunction "1_1") (pintype "passive"))
    )
    (net (code "34") (name "COL16_DRV") (class "Default")
      (node (ref "IC7") (pin "6") (pinfunction "QG_6") (pintype "tri_state"))
      (node (ref "R16") (pin "1") (pinfunction "1_1") (pintype "passive"))
    )
    (net (code "35") (name "COL17") (class "Default")
      (node (ref "D113") (pin "A") (pinfunction "A_A") (pintype "passive"))
      (node (ref "D114") (pin "A") (pinfunction "A_A") (pintype "passive"))
      (node (ref "D115") (pin "A") (pinfunction "A_A") (pintype "passive"))
      (node (ref "D116") (pin "A") (pinfunction "A_A") (pintype "passive"))
      (node (ref "D117") (pin "A") (pinfunction "A_A") (pintype "passive"))
      (node (ref "D118") (pin "A") (pinfunction "A_A") (pintype "passive"))
      (node (ref "D119") (pin "A") (pinfunction "A_A") (pintype "passive"))
      (node (ref "R49") (pin "1") (pinfunction "1_1") (pintype "passive"))
    )
    (net (code "36") (name "COL17_DRV") (class "Default")
      (node (ref "IC7") (pin "7") (pinfunction "QH_7") (pintype "tri_state"))
      (node (ref "R17") (pin "1") (pinfunction "1_1") (pintype "passive"))
    )
    (net (code "37") (name "COL18") (class "Default")
      (node (ref "D120") (pin "A") (pinfunction "A_A") (pintype "passive"))
      (node (ref "D121") (pin "A") (pinfunction "A_A") (pintype "passive"))
      (node (ref "D122") (pin "A") (pinfunction "A_A") (pintype "passive"))
      (node (ref "D123") (pin "A") (pinfunction "A_A") (pintype "passive"))
      (node (ref "D124") (pin "A") (pinfunction "A_A") (pintype "passive"))
      (node (ref "D125") (pin "A") (pinfunction "A_A") (pintype "passive"))
      (node (ref "D126") (pin "A") (pinfunction "A_A") (pintype "passive"))
      (node (ref "R50") (pin "1") (pinfunction "1_1") (pintype "passive"))
    )
    (net (code "38") (name "COL18_DRV") (class "Default")
      (node (ref "IC8") (pin "15") (pinfunction "QA_15") (pintype "tri_state"))
      (node (ref "R18") (pin "1") (pinfunction "1_1") (pintype "passive"))
    )
    (net (code "39") (name "COL19") (class "Default")
      (node (ref "D127") (pin "A") (pinfunction "A_A") (pintype "passive"))
      (node (ref "D128") (pin "A") (pinfunction "A_A") (pintype "passive"))
      (node (ref "D129") (pin "A") (pinfunction "A_A") (pintype "passive"))
      (node (ref "D130") (pin "A") (pinfunction "A_A") (pintype "passive"))
      (node (ref "D131") (pin "A") (pinfunction "A_A") (pintype "passive"))
      (node (ref "D132") (pin "A") (pinfunction "A_A") (pintype "passive"))
      (node (ref "D133") (pin "A") (pinfunction "A_A") (pintype "passive"))
      (node (ref "R51") (pin "1") (pinfunction "1_1") (pintype "passive"))
    )
    (net (code "40") (name "COL19_DRV") (class "Default")
      (node (ref "IC8") (pin "1") (pinfunction "QB_1") (pintype "tri_state"))
      (node (ref "R19") (pin "1") (pinfunction "1_1") (pintype "passive"))
    )
    (net (code "41") (name "COL20") (class "Default")
      (node (ref "D134") (pin "A") (pinfunction "A_A") (pintype "passive"))
      (node (ref "D135") (pin "A") (pinfunction "A_A") (pintype "passive"))
      (node (ref "D136") (pin "A") (pinfunction "A_A") (pintype "passive"))
      (node (ref "D137") (pin "A") (pinfunction "A_A") (pintype "passive"))
      (node (ref "D138") (pin "A") (pinfunction "A_A") (pintype "passive"))
      (node (ref "D139") (pin "A") (pinfunction "A_A") (pintype "passive"))
      (node (ref "D140") (pin "A") (pinfunction "A_A") (pintype "passive"))
      (node (ref "R52") (pin "1") (pinfunction "1_1") (pintype "passive"))
    )
    (net (code "42") (name "COL20_DRV") (class "Default")
      (node (ref "IC8") (pin "2") (pinfunction "QC_2") (pintype "tri_state"))
      (node (ref "R20") (pin "1") (pinfunction "1_1") (pintype "passive"))
    )
    (net (code "43") (name "COL21") (class "Default")
      (node (ref "D141") (pin "A") (pinfunction "A_A") (pintype "passive"))
      (node (ref "D142") (pin "A") (pinfunction "A_A") (pintype "passive"))
      (node (ref "D143") (pin "A") (pinfunction "A_A") (pintype "passive"))
      (node (ref "D144") (pin "A") (pinfunction "A_A") (pintype "passive"))
      (node (ref "D145") (pin "A") (pinfunction "A_A") (pintype "passive"))
      (node (ref "D146") (pin "A") (pinfunction "A_A") (pintype "passive"))
      (node (ref "D147") (pin "A") (pinfunction "A_A") (pintype "passive"))
      (node (ref "R73") (pin "1") (pinfunction "1_1") (pintype "passive"))
    )
    (net (code "44") (name "COL21_DRV") (class "Default")
      (node (ref "IC8") (pin "3") (pinfunction "QD_3") (pintype "tri_state"))
      (node (ref "R21") (pin "1") (pinfunction "1_1") (pintype "passive"))
    )
    (net (code "45") (name "COL22") (class "Default")
      (node (ref "D148") (pin "A") (pinfunction "A_A") (pintype "passive"))
      (node (ref "D149") (pin "A") (pinfunction "A_A") (pintype "passive"))
      (node (ref "D150") (pin "A") (pinfunction "A_A") (pintype "passive"))
      (node (ref "D151") (pin "A") (pinfunction "A_A") (pintype "passive"))
      (node (ref "D152") (pin "A") (pinfunction "A_A") (pintype "passive"))
      (node (ref "D153") (pin "A") (pinfunction "A_A") (pintype "passive"))
      (node (ref "D154") (pin "A") (pinfunction "A_A") (pintype "passive"))
      (node (ref "R74") (pin "1") (pinfunction "1_1") (pintype "passive"))
    )
    (net (code "46") (name "COL22_DRV") (class "Default")
      (node (ref "IC8") (pin "4") (pinfunction "QE_4") (pintype "tri_state"))
      (node (ref "R22") (pin "1") (pinfunction "1_1") (pintype "passive"))
    )
    (net (code "47") (name "COL23") (class "Default")
      (node (ref "D155") (pin "A") (pinfunction "A_A") (pintype "passive"))
      (node (ref "D156") (pin "A") (pinfunction "A_A") (pintype "passive"))
      (node (ref "D157") (pin "A") (pinfunction "A_A") (pintype "passive"))
      (node (ref "D158") (pin "A") (pinfunction "A_A") (pintype "passive"))
      (node (ref "D159") (pin "A") (pinfunction "A_A") (pintype "passive"))
      (node (ref "D160") (pin "A") (pinfunction "A_A") (pintype "passive"))
      (node (ref "D161") (pin "A") (pinfunction "A_A") (pintype "passive"))
      (node (ref "R75") (pin "1") (pinfunction "1_1") (pintype "passive"))
    )
    (net (code "48") (name "COL23_DRV") (class "Default")
      (node (ref "IC8") (pin "5") (pinfunction "QF_5") (pintype "tri_state"))
      (node (ref "R23") (pin "1") (pinfunction "1_1") (pintype "passive"))
    )
    (net (code "49") (name "COL24") (class "Default")
      (node (ref "D162") (pin "A") (pinfunction "A_A") (pintype "passive"))
      (node (ref "D163") (pin "A") (pinfunction "A_A") (pintype "passive"))
      (node (ref "D164") (pin "A") (pinfunction "A_A") (pintype "passive"))
      (node (ref "D165") (pin "A") (pinfunction "A_A") (pintype "passive"))
      (node (ref "D166") (pin "A") (pinfunction "A_A") (pintype "passive"))
      (node (ref "D167") (pin "A") (pinfunction "A_A") (pintype "passive"))
      (node (ref "D168") (pin "A") (pinfunction "A_A") (pintype "passive"))
      (node (ref "R76") (pin "1") (pinfunction "1_1") (pintype "passive"))
    )
    (net (code "50") (name "COL24_DRV") (class "Default")
      (node (ref "IC8") (pin "6") (pinfunction "QG_6") (pintype "tri_state"))
      (node (ref "R24") (pin "1") (pinfunction "1_1") (pintype "passive"))
    )
    (net (code "51") (name "COL25") (class "Default")
      (node (ref "D169") (pin "A") (pinfunction "A_A") (pintype "passive"))
      (node (ref "D170") (pin "A") (pinfunction "A_A") (pintype "passive"))
      (node (ref "D171") (pin "A") (pinfunction "A_A") (pintype "passive"))
      (node (ref "D172") (pin "A") (pinfunction "A_A") (pintype "passive"))
      (node (ref "D173") (pin "A") (pinfunction "A_A") (pintype "passive"))
      (node (ref "D174") (pin "A") (pinfunction "A_A") (pintype "passive"))
      (node (ref "D175") (pin "A") (pinfunction "A_A") (pintype "passive"))
      (node (ref "R77") (pin "1") (pinfunction "1_1") (pintype "passive"))
    )
    (net (code "52") (name "COL25_DRV") (class "Default")
      (node (ref "IC8") (pin "7") (pinfunction "QH_7") (pintype "tri_state"))
      (node (ref "R25") (pin "1") (pinfunction "1_1") (pintype "passive"))
    )
    (net (code "53") (name "DATA") (class "Default")
      (node (ref "IC5") (pin "14") (pinfunction "SER_14") (pintype "input"))
      (node (ref "R90") (pin "2") (pinfunction "2_2") (pintype "passive"))
      (node (ref "U1") (pin "13") (pinfunction "B1_13") (pintype "bidirectional"))
    )
    (net (code "54") (name "DATA_A") (class "Default")
      (node (ref "JP2") (pin "1") (pinfunction "1_1") (pintype "passive"))
      (node (ref "R90") (pin "1") (pinfunction "1_1") (pintype "passive"))
      (node (ref "U1") (pin "2") (pinfunction "A1_2") (pintype "bidirectional"))
    )
    (net (code "55") (name "DATA_OUT") (class "Default")
      (node (ref "IC8") (pin "9") (pinfunction "QH*_9") (pintype "tri_state"))
      (node (ref "JP3") (pin "1") (pinfunction "1_1") (pintype "passive"))
    )
    (net (code "56") (name "FB") (class "Default")
      (node (ref "C20") (pin "2") (pinfunction "2_2") (pintype "passive"))
      (node (ref "R96") (pin "1") (pinfunction "1_1") (pintype "passive"))
      (node (ref "R97") (pin "2") (pinfunction "2_2") (pintype "passive"))
      (node (ref "U4") (pin "4") (pinfunction "FB_4") (pintype "bidirectional"))
    )
    (net (code "57") (name "GND") (class "Default")
      (node (ref "C1") (pin "2") (pinfunction "2_2") (pintype "passive"))
      (node (ref "C15") (pin "2") (pinfunction "2_2") (pintype "passive"))
      (node (ref "C16") (pin "2") (pinfunction "2_2") (pintype "passive"))
      (node (ref "C17") (pin "2") (pinfunction "2_2") (pintype "passive"))
      (node (ref "C19") (pin "2") (pinfunction "2_2") (pintype "passive"))
      (node (ref "C2") (pin "2") (pinfunction "2_2") (pintype "passive"))
      (node (ref "C21") (pin "2") (pinfunction "2_2") (pintype "passive"))
      (node (ref "C3") (pin "2") (pinfunction "2_2") (pintype "passive"))
      (node (ref "C4") (pin "2") (pinfunction "2_2") (pintype "passive"))
      (node (ref "C5") (pin "2") (pinfunction "2_2") (pintype "passive"))
      (node (ref "C6") (pin "2") (pinfunction "2_2") (pintype "passive"))
      (node (ref "C7") (pin "2") (pinfunction "2_2") (pintype "passive"))
      (node (ref "IC5") (pin "8") (pinfunction "GND_8") (pintype "power_in"))
      (node (ref "IC6") (pin "8") (pinfunction "GND_8") (pintype "power_in"))
      (node (ref "IC7") (pin "8") (pinfunction "GND_8") (pintype "power_in"))
      (node (ref "IC8") (pin "8") (pinfunction "GND_8") (pintype "power_in"))
      (node (ref "JP2") (pin "10") (pinfunction "10_10") (pintype "passive"))
      (node (ref "JP3") (pin "10") (pinfunction "10_10") (pintype "passive"))
      (node (ref "P2") (pin "1") (pinfunction "1_1") (pintype "passive"))
      (node (ref "P4") (pin "1") (pinfunction "1_1") (pintype "passive"))
      (node (ref "Q27") (pin "S1") (pinfunction "S1_S1") (pintype "passive"))
      (node (ref "Q27") (pin "S2") (pinfunction "S2_S2") (pintype "passive"))
      (node (ref "Q27") (pin "S3") (pinfunction "S3_S3") (pintype "passive"))
      (node (ref "Q28") (pin "3") (pinfunction "S_3") (pintype "passive"))
      (node (ref "Q29") (pin "3") (pinfunction "S_3") (pintype "passive"))
      (node (ref "Q30") (pin "3") (pinfunction "S_3") (pintype "passive"))
      (node (ref "Q31") (pin "3") (pinfunction "S_3") (pintype "passive"))
      (node (ref "Q32") (pin "3") (pinfunction "S_3") (pintype "passive"))
      (node (ref "Q33") (pin "3") (pinfunction "S_3") (pintype "passive"))
      (node (ref "Q34") (pin "3") (pinfunction "S_3") (pintype "passive"))
      (node (ref "R83") (pin "2") (pinfunction "2_2") (pintype "passive"))
      (node (ref "R84") (pin "2") (pinfunction "2_2") (pintype "passive"))
      (node (ref "R85") (pin "2") (pinfunction "2_2") (pintype "passive"))
      (node (ref "R86") (pin "2") (pinfunction "2_2") (pintype "passive"))
      (node (ref "R87") (pin "2") (pinfunction "2_2") (pintype "passive"))
      (node (ref "R88") (pin "2") (pinfunction "2_2") (pintype "passive"))
      (node (ref "R89") (pin "2") (pinfunction "2_2") (pintype "passive"))
      (node (ref "R97") (pin "1") (pinfunction "1_1") (pintype "passive"))
      (node (ref "R99") (pin "2") (pinfunction "2_2") (pintype "passive"))
      (node (ref "U1") (pin "7") (pinfunction "GND_7") (pintype "bidirectional"))
      (node (ref "U2") (pin "1") (pinfunction "GND_1") (pintype "input"))
      (node (ref "U4") (pin "14") (pinfunction "PGND_14") (pintype "bidirectional"))
      (node (ref "U4") (pin "5") (pinfunction "SGND_5") (pintype "bidirectional"))
      (node (ref "U4") (pin "9") (pinfunction "SGND_9") (pintype "bidirectional"))
      (node (ref "U4") (pin "EP") (pinfunction "EP_EP") (pintype "bidirectional"))
    )
    (net (code "58") (name "HG") (class "Default")
      (node (ref "Q26") (pin "G") (pinfunction "G_G") (pintype "passive"))
      (node (ref "U4") (pin "11") (pinfunction "HG_11") (pintype "bidirectional"))
    )
    (net (code "59") (name "LATCH") (class "Default")
      (node (ref "IC5") (pin "12") (pinfunction "RCK_12") (pintype "input"))
      (node (ref "IC6") (pin "12") (pinfunction "RCK_12") (pintype "input"))
      (node (ref "IC7") (pin "12") (pinfunction "RCK_12") (pintype "input"))
      (node (ref "IC8") (pin "12") (pinfunction "RCK_12") (pintype "input"))
      (node (ref "JP3") (pin "3") (pinfunction "3_3") (pintype "passive"))
      (node (ref "R92") (pin "2") (pinfunction "2_2") (pintype "passive"))
      (node (ref "U1") (pin "11") (pinfunction "B3_11") (pintype "bidirectional"))
    )
    (net (code "60") (name "LATCH_A") (class "Default")
      (node (ref "JP2") (pin "3") (pinfunction "3_3") (pintype "passive"))
      (node (ref "R92") (pin "1") (pinfunction "1_1") (pintype "passive"))
      (node (ref "U1") (pin "4") (pinfunction "A3_4") (pintype "bidirectional"))
    )
    (net (code "61") (name "LG") (class "Default")
      (node (ref "Q27") (pin "G") (pinfunction "G_G") (pintype "passive"))
      (node (ref "U4") (pin "13") (pinfunction "LG_13") (pintype "bidirectional"))
    )
    (net (code "62") (name "Net-(IC5A-QH*)") (class "Default")
      (node (ref "IC5") (pin "9") (pinfunction "QH*_9") (pintype "tri_state"))
      (node (ref "IC6") (pin "14") (pinfunction "SER_14") (pintype "input"))
    )
    (net (code "63") (name "Net-(IC6A-QH*)") (class "Default")
      (node (ref "IC6") (pin "9") (pinfunction "QH*_9") (pintype "tri_state"))
      (node (ref "IC7") (pin "14") (pinfunction "SER_14") (pintype "input"))
    )
    (net (code "64") (name "Net-(IC7A-QH*)") (class "Default")
      (node (ref "IC7") (pin "9") (pinfunction "QH*_9") (pintype "tri_state"))
      (node (ref "IC8") (pin "14") (pinfunction "SER_14") (pintype "input"))
    )
    (net (code "65") (name "Net-(L2-1)") (class "Default")
      (node (ref "C18") (pin "2") (pinfunction "2_2") (pintype "passive"))
      (node (ref "L2") (pin "P$1") (pinfunction "1_P$1") (pintype "passive"))
      (node (ref "Q26") (pin "S1") (pinfunction "S1_S1") (pintype "passive"))
      (node (ref "Q26") (pin "S2") (pinfunction "S2_S2") (pintype "passive"))
      (node (ref "Q26") (pin "S3") (pinfunction "S3_S3") (pintype "passive"))
      (node (ref "Q27") (pin "D1") (pinfunction "D1_D1") (pintype "passive"))
      (node (ref "Q27") (pin "D2") (pinfunction "D2_D2") (pintype "passive"))
      (node (ref "Q27") (pin "D3") (pinfunction "D3_D3") (pintype "passive"))
      (node (ref "Q27") (pin "D4") (pinfunction "D4_D4") (pintype "passive"))
      (node (ref "R95") (pin "1") (pinfunction "1_1") (pintype "passive"))
      (node (ref "U4") (pin "10") (pinfunction "SW_10") (pintype "bidirectional"))
    )
    (net (code "66") (name "Net-(Q1-D)") (class "Default")
      (node (ref "Q1") (pin "3") (pinfunction "D_3") (pintype "passive"))
      (node (ref "R1") (pin "2") (pinfunction "2_2") (pintype "passive"))
    )
    (net (code "67") (name "Net-(Q1-G)") (class "Default")
      (node (ref "Q1") (pin "1") (pinfunction "G_1") (pintype "passive"))
      (node (ref "R33") (pin "2") (pinfunction "2_2") (pintype "passive"))
      (node (ref "R53") (pin "1") (pinfunction "1_1") (pintype "passive"))
    )
    (net (code "68") (name "Net-(Q2-D)") (class "Default")
      (node (ref "Q2") (pin "3") (pinfunction "D_3") (pintype "passive"))
      (node (ref "R2") (pin "2") (pinfunction "2_2") (pintype "passive"))
    )
    (net (code "69") (name "Net-(Q2-G)") (class "Default")
      (node (ref "Q2") (pin "1") (pinfunction "G_1") (pintype "passive"))
      (node (ref "R34") (pin "2") (pinfunction "2_2") (pintype "passive"))
      (node (ref "R54") (pin "1") (pinfunction "1_1") (pintype "passive"))
    )
    (net (code "70") (name "Net-(Q3-D)") (class "Default")
      (node (ref "Q3") (pin "3") (pinfunction "D_3") (pintype "passive"))
      (node (ref "R3") (pin "2") (pinfunction "2_2") (pintype "passive"))
    )
    (net (code "71") (name "Net-(Q3-G)") (class "Default")
      (node (ref "Q3") (pin "1") (pinfunction "G_1") (pintype "passive"))
      (node (ref "R35") (pin "2") (pinfunction "2_2") (pintype "passive"))
      (node (ref "R55") (pin "1") (pinfunction "1_1") (pintype "passive"))
    )
    (net (code "72") (name "Net-(Q4-D)") (class "Default")
      (node (ref "Q4") (pin "3") (pinfunction "D_3") (pintype "passive"))
      (node (ref "R4") (pin "2") (pinfunction "2_2") (pintype "passive"))
    )
    (net (code "73") (name "Net-(Q4-G)") (class "Default")
      (node (ref "Q4") (pin "1") (pinfunction "G_1") (pintype "passive"))
      (node (ref "R36") (pin "2") (pinfunction "2_2") (pintype "passive"))
      (node (ref "R56") (pin "1") (pinfunction "1_1") (pintype "passive"))
    )
    (net (code "74") (name "Net-(Q5-D)") (class "Default")
      (node (ref "Q5") (pin "3") (pinfunction "D_3") (pintype "passive"))
      (node (ref "R5") (pin "2") (pinfunction "2_2") (pintype "passive"))
    )
    (net (code "75") (name "Net-(Q5-G)") (class "Default")
      (node (ref "Q5") (pin "1") (pinfunction "G_1") (pintype "passive"))
      (node (ref "R37") (pin "2") (pinfunction "2_2") (pintype "passive"))
      (node (ref "R57") (pin "1") (pinfunction "1_1") (pintype "passive"))
    )
    (net (code "76") (name "Net-(Q6-D)") (class "Default")
      (node (ref "Q6") (pin "3") (pinfunction "D_3") (pintype "passive"))
      (node (ref "R6") (pin "2") (pinfunction "2_2") (pintype "passive"))
    )
    (net (code "77") (name "Net-(Q6-G)") (class "Default")
      (node (ref "Q6") (pin "1") (pinfunction "G_1") (pintype "passive"))
      (node (ref "R38") (pin "2") (pinfunction "2_2") (pintype "passive"))
      (node (ref "R58") (pin "1") (pinfunction "1_1") (pintype "passive"))
    )
    (net (code "78") (name "Net-(Q7-D)") (class "Default")
      (node (ref "Q7") (pin "3") (pinfunction "D_3") (pintype "passive"))
      (node (ref "R7") (pin "2") (pinfunction "2_2") (pintype "passive"))
    )
    (net (code "79") (name "Net-(Q7-G)") (class "Default")
      (node (ref "Q7") (pin "1") (pinfunction "G_1") (pintype "passive"))
      (node (ref "R39") (pin "2") (pinfunction "2_2") (pintype "passive"))
      (node (ref "R59") (pin "1") (pinfunction "1_1") (pintype "passive"))
    )
    (net (code "80") (name "Net-(Q8-D)") (class "Default")
      (node (ref "Q8") (pin "3") (pinfunction "D_3") (pintype "passive"))
      (node (ref "R8") (pin "2") (pinfunction "2_2") (pintype "passive"))
    )
    (net (code "81") (name "Net-(Q8-G)") (class "Default")
      (node (ref "Q8") (pin "1") (pinfunction "G_1") (pintype "passive"))
      (node (ref "R40") (pin "2") (pinfunction "2_2") (pintype "passive"))
      (node (ref "R60") (pin "1") (pinfunction "1_1") (pintype "passive"))
    )
    (net (code "82") (name "Net-(Q9-D)") (class "Default")
      (node (ref "Q9") (pin "3") (pinfunction "D_3") (pintype "passive"))
      (node (ref "R9") (pin "2") (pinfunction "2_2") (pintype "passive"))
    )
    (net (code "83") (name "Net-(Q9-G)") (class "Default")
      (node (ref "Q9") (pin "1") (pinfunction "G_1") (pintype "passive"))
      (node (ref "R41") (pin "2") (pinfunction "2_2") (pintype "passive"))
      (node (ref "R61") (pin "1") (pinfunction "1_1") (pintype "passive"))
    )
    (net (code "84") (name "Net-(Q10-D)") (class "Default")
      (node (ref "Q10") (pin "3") (pinfunction "D_3") (pintype "passive"))
      (node (ref "R10") (pin "2") (pinfunction "2_2") (pintype "passive"))
    )
    (net (code "85") (name "Net-(Q10-G)") (class "Default")
      (node (ref "Q10") (pin "1") (pinfunction "G_1") (pintype "passive"))
      (node (ref "R42") (pin "2") (pinfunction "2_2") (pintype "passive"))
      (node (ref "R62") (pin "1") (pinfunction "1_1") (pintype "passive"))
    )
    (net (code "86") (name "Net-(Q11-D)") (class "Default")
      (node (ref "Q11") (pin "3") (pinfunction "D_3") (pintype "passive"))
      (node (ref "R43") (pin "2") (pinfunction "2_2") (pintype "passive"))
    )
    (net (code "87") (name "Net-(Q11-G)") (class "Default")
      (node (ref "Q11") (pin "1") (pinfunction "G_1") (pintype "passive"))
      (node (ref "R11") (pin "2") (pinfunction "2_2") (pintype "passive"))
      (node (ref "R63") (pin "1") (pinfunction "1_1") (pintype "passive"))
    )
    (net (code "88") (name "Net-(Q12-D)") (class "Default")
      (node (ref "Q12") (pin "3") (pinfunction "D_3") (pintype "passive"))
      (node (ref "R44") (pin "2") (pinfunction "2_2") (pintype "passive"))
    )
    (net (code "89") (name "Net-(Q12-G)") (class "Default")
      (node (ref "Q12") (pin "1") (pinfunction "G_1") (pintype "passive"))
      (node (ref "R12") (pin "2") (pinfunction "2_2") (pintype "passive"))
      (node (ref "R64") (pin "1") (pinfunction "1_1") (pintype "passive"))
    )
    (net (code "90") (name "Net-(Q13-D)") (class "Default")
      (node (ref "Q13") (pin "3") (pinfunction "D_3") (pintype "passive"))
      (node (ref "R45") (pin "2") (pinfunction "2_2") (pintype "passive"))
    )
    (net (code "91") (name "Net-(Q13-G)") (class "Default")
      (node (ref "Q13") (pin "1") (pinfunction "G_1") (pintype "passive"))
      (node (ref "R13") (pin "2") (pinfunction "2_2") (pintype "passive"))
      (node (ref "R65") (pin "1") (pinfunction "1_1") (pintype "passive"))
    )
    (net (code "92") (name "Net-(Q14-D)") (class "Default")
      (node (ref "Q14") (pin "3") (pinfunction "D_3") (pintype "passive"))
      (node (ref "R46") (pin "2") (pinfunction "2_2") (pintype "passive"))
    )
    (net (code "93") (name "Net-(Q14-G)") (class "Default")
      (node (ref "Q14") (pin "1") (pinfunction "G_1") (pintype "passive"))
      (node (ref "R14") (pin "2") (pinfunction "2_2") (pintype "passive"))
      (node (ref "R66") (pin "1") (pinfunction "1_1") (pintype "passive"))
    )
    (net (code "94") (name "Net-(Q15-D)") (class "Default")
      (node (ref "Q15") (pin "3") (pinfunction "D_3") (pintype "passive"))
      (node (ref "R47") (pin "2") (pinfunction "2_2") (pintype "passive"))
    )
    (net (code "95") (name "Net-(Q15-G)") (class "Default")
      (node (ref "Q15") (pin "1") (pinfunction "G_1") (pintype "passive"))
      (node (ref "R15") (pin "2") (pinfunction "2_2") (pintype "passive"))
      (node (ref "R67") (pin "1") (pinfunction "1_1") (pintype "passive"))
    )
    (net (code "96") (name "Net-(Q16-D)") (class "Default")
      (node (ref "Q16") (pin "3") (pinfunction "D_3") (pintype "passive"))
      (node (ref "R48") (pin "2") (pinfunction "2_2") (pintype "passive"))
    )
    (net (code "97") (name "Net-(Q16-G)") (class "Default")
      (node (ref "Q16") (pin "1") (pinfunction "G_1") (pintype "passive"))
      (node (ref "R16") (pin "2") (pinfunction "2_2") (pintype "passive"))
      (node (ref "R68") (pin "1") (pinfunction "1_1") (pintype "passive"))
    )
    (net (code "98") (name "Net-(Q17-D)") (class "Default")
      (node (ref "Q17") (pin "3") (pinfunction "D_3") (pintype "passive"))
      (node (ref "R49") (pin "2") (pinfunction "2_2") (pintype "passive"))
    )
    (net (code "99") (name "Net-(Q17-G)") (class "Default")
      (node (ref "Q17") (pin "1") (pinfunction "G_1") (pintype "passive"))
      (node (ref "R17") (pin "2") (pinfunction "2_2") (pintype "passive"))
      (node (ref "R69") (pin "1") (pinfunction "1_1") (pintype "passive"))
    )
    (net (code "100") (name "Net-(Q18-D)") (class "Default")
      (node (ref "Q18") (pin "3") (pinfunction "D_3") (pintype "passive"))
      (node (ref "R50") (pin "2") (pinfunction "2_2") (pintype "passive"))
    )
    (net (code "101") (name "Net-(Q18-G)") (class "Default")
      (node (ref "Q18") (pin "1") (pinfunction "G_1") (pintype "passive"))
      (node (ref "R18") (pin "2") (pinfunction "2_2") (pintype "passive"))
      (node (ref "R70") (pin "1") (pinfunction "1_1") (pintype "passive"))
    )
    (net (code "102") (name "Net-(Q19-D)") (class "Default")
      (node (ref "Q19") (pin "3") (pinfunction "D_3") (pintype "passive"))
      (node (ref "R51") (pin "2") (pinfunction "2_2") (pintype "passive"))
    )
    (net (code "103") (name "Net-(Q19-G)") (class "Default")
      (node (ref "Q19") (pin "1") (pinfunction "G_1") (pintype "passive"))
      (node (ref "R19") (pin "2") (pinfunction "2_2") (pintype "passive"))
      (node (ref "R71") (pin "1") (pinfunction "1_1") (pintype "passive"))
    )
    (net (code "104") (name "Net-(Q20-D)") (class "Default")
      (node (ref "Q20") (pin "3") (pinfunction "D_3") (pintype "passive"))
      (node (ref "R52") (pin "2") (pinfunction "2_2") (pintype "passive"))
    )
    (net (code "105") (name "Net-(Q20-G)") (class "Default")
      (node (ref "Q20") (pin "1") (pinfunction "G_1") (pintype "passive"))
      (node (ref "R20") (pin "2") (pinfunction "2_2") (pintype "passive"))
      (node (ref "R72") (pin "1") (pinfunction "1_1") (pintype "passive"))
    )
    (net (code "106") (name "Net-(Q21-D)") (class "Default")
      (node (ref "Q21") (pin "3") (pinfunction "D_3") (pintype "passive"))
      (node (ref "R73") (pin "2") (pinfunction "2_2") (pintype "passive"))
    )
    (net (code "107") (name "Net-(Q21-G)") (class "Default")
      (node (ref "Q21") (pin "1") (pinfunction "G_1") (pintype "passive"))
      (node (ref "R21") (pin "2") (pinfunction "2_2") (pintype "passive"))
      (node (ref "R78") (pin "1") (pinfunction "1_1") (pintype "passive"))
    )
    (net (code "108") (name "Net-(Q22-D)") (class "Default")
      (node (ref "Q22") (pin "3") (pinfunction "D_3") (pintype "passive"))
      (node (ref "R74") (pin "2") (pinfunction "2_2") (pintype "passive"))
    )
    (net (code "109") (name "Net-(Q22-G)") (class "Default")
      (node (ref "Q22") (pin "1") (pinfunction "G_1") (pintype "passive"))
      (node (ref "R22") (pin "2") (pinfunction "2_2") (pintype "passive"))
      (node (ref "R79") (pin "1") (pinfunction "1_1") (pintype "passive"))
    )
    (net (code "110") (name "Net-(Q23-D)") (class "Default")
      (node (ref "Q23") (pin "3") (pinfunction "D_3") (pintype "passive"))
      (node (ref "R75") (pin "2") (pinfunction "2_2") (pintype "passive"))
    )
    (net (code "111") (name "Net-(Q23-G)") (class "Default")
      (node (ref "Q23") (pin "1") (pinfunction "G_1") (pintype "passive"))
      (node (ref "R23") (pin "2") (pinfunction "2_2") (pintype "passive"))
      (node (ref "R80") (pin "1") (pinfunction "1_1") (pintype "passive"))
    )
    (net (code "112") (name "Net-(Q24-D)") (class "Default")
      (node (ref "Q24") (pin "3") (pinfunction "D_3") (pintype "passive"))
      (node (ref "R76") (pin "2") (pinfunction "2_2") (pintype "passive"))
    )
    (net (code "113") (name "Net-(Q24-G)") (class "Default")
      (node (ref "Q24") (pin "1") (pinfunction "G_1") (pintype "passive"))
      (node (ref "R24") (pin "2") (pinfunction "2_2") (pintype "passive"))
      (node (ref "R81") (pin "1") (pinfunction "1_1") (pintype "passive"))
    )
    (net (code "114") (name "Net-(Q25-D)") (class "Default")
      (node (ref "Q25") (pin "3") (pinfunction "D_3") (pintype "passive"))
      (node (ref "R77") (pin "2") (pinfunction "2_2") (pintype "passive"))
    )
    (net (code "115") (name "Net-(Q25-G)") (class "Default")
      (node (ref "Q25") (pin "1") (pinfunction "G_1") (pintype "passive"))
      (node (ref "R25") (pin "2") (pinfunction "2_2") (pintype "passive"))
      (node (ref "R82") (pin "1") (pinfunction "1_1") (pintype "passive"))
    )
    (net (code "116") (name "Net-(Q28-G)") (class "Default")
      (node (ref "Q28") (pin "1") (pinfunction "G_1") (pintype "passive"))
      (node (ref "R26") (pin "1") (pinfunction "1_1") (pintype "passive"))
      (node (ref "R83") (pin "1") (pinfunction "1_1") (pintype "passive"))
    )
    (net (code "117") (name "Net-(Q29-G)") (class "Default")
      (node (ref "Q29") (pin "1") (pinfunction "G_1") (pintype "passive"))
      (node (ref "R27") (pin "1") (pinfunction "1_1") (pintype "passive"))
      (node (ref "R84") (pin "1") (pinfunction "1_1") (pintype "passive"))
    )
    (net (code "118") (name "Net-(Q30-G)") (class "Default")
      (node (ref "Q30") (pin "1") (pinfunction "G_1") (pintype "passive"))
      (node (ref "R28") (pin "1") (pinfunction "1_1") (pintype "passive"))
      (node (ref "R85") (pin "1") (pinfunction "1_1") (pintype "passive"))
    )
    (net (code "119") (name "Net-(Q31-G)") (class "Default")
      (node (ref "Q31") (pin "1") (pinfunction "G_1") (pintype "passive"))
      (node (ref "R29") (pin "1") (pinfunction "1_1") (pintype "passive"))
      (node (ref "R86") (pin "1") (pinfunction "1_1") (pintype "passive"))
    )
    (net (code "120") (name "Net-(Q32-G)") (class "Default")
      (node (ref "Q32") (pin "1") (pinfunction "G_1") (pintype "passive"))
      (node (ref "R30") (pin "1") (pinfunction "1_1") (pintype "passive"))
      (node (ref "R87") (pin "1") (pinfunction "1_1") (pintype "passive"))
    )
    (net (code "121") (name "Net-(Q33-G)") (class "Default")
      (node (ref "Q33") (pin "1") (pinfunction "G_1") (pintype "passive"))
      (node (ref "R31") (pin "1") (pinfunction "1_1") (pintype "passive"))
      (node (ref "R88") (pin "1") (pinfunction "1_1") (pintype "passive"))
    )
    (net (code "122") (name "Net-(Q34-G)") (class "Default")
      (node (ref "Q34") (pin "1") (pinfunction "G_1") (pintype "passive"))
      (node (ref "R32") (pin "1") (pinfunction "1_1") (pintype "passive"))
      (node (ref "R89") (pin "1") (pinfunction "1_1") (pintype "passive"))
    )
    (net (code "123") (name "Net-(U4-BST)") (class "Default")
      (node (ref "C18") (pin "1") (pinfunction "1_1") (pintype "passive"))
      (node (ref "U4") (pin "12") (pinfunction "BST_12") (pintype "bidirectional"))
    )
    (net (code "124") (name "Net-(U4-ILIM)") (class "Default")
      (node (ref "R95") (pin "2") (pinfunction "2_2") (pintype "passive"))
      (node (ref "U4") (pin "8") (pinfunction "ILIM_8") (pintype "bidirectional"))
    )
    (net (code "125") (name "Net-(U4-RON)") (class "Default")
      (node (ref "R94") (pin "1") (pinfunction "1_1") (pintype "passive"))
      (node (ref "U4") (pin "7") (pinfunction "RON_7") (pintype "bidirectional"))
    )
    (net (code "126") (name "Net-(U4-SS)") (class "Default")
      (node (ref "C16") (pin "1") (pinfunction "1_1") (pintype "passive"))
      (node (ref "U4") (pin "6") (pinfunction "SS_6") (pintype "bidirectional"))
    )
    (net (code "127") (name "Net-(U4-VCC)") (class "Default")
      (node (ref "C17") (pin "1") (pinfunction "1_1") (pintype "passive"))
      (node (ref "U4") (pin "1") (pinfunction "VCC_1") (pintype "bidirectional"))
    )
    (net (code "128") (name "OE#") (class "Default")
      (node (ref "IC5") (pin "13") (pinfunction "G_13") (pintype "input"))
      (node (ref "IC6") (pin "13") (pinfunction "G_13") (pintype "input"))
      (node (ref "IC7") (pin "13") (pinfunction "G_13") (pintype "input"))
      (node (ref "IC8") (pin "13") (pinfunction "G_13") (pintype "input"))
      (node (ref "JP3") (pin "4") (pinfunction "4_4") (pintype "passive"))
      (node (ref "R93") (pin "2") (pinfunction "2_2") (pintype "passive"))
      (node (ref "R98") (pin "2") (pinfunction "2_2") (pintype "passive"))
      (node (ref "R99") (pin "1") (pinfunction "1_1") (pintype "passive"))
      (node (ref "U1") (pin "10") (pinfunction "B4_10") (pintype "bidirectional"))
    )
    (net (code "129") (name "OE#_A") (class "Default")
      (node (ref "JP2") (pin "4") (pinfunction "4_4") (pintype "passive"))
      (node (ref "R98") (pin "1") (pinfunction "1_1") (pintype "passive"))
      (node (ref "U1") (pin "5") (pinfunction "A4_5") (pintype "bidirectional"))
    )
    (net (code "130") (name "ROW1") (class "Default")
      (node (ref "D1") (pin "C") (pinfunction "C_C") (pintype "passive"))
      (node (ref "D106") (pin "C") (pinfunction "C_C") (pintype "passive"))
      (node (ref "D113") (pin "C") (pinfunction "C_C") (pintype "passive"))
      (node (ref "D120") (pin "C") (pinfunction "C_C") (pintype "passive"))
      (node (ref "D127") (pin "C") (pinfunction "C_C") (pintype "passive"))
      (node (ref "D134") (pin "C") (pinfunction "C_C") (pintype "passive"))
      (node (ref "D141") (pin "C") (pinfunction "C_C") (pintype "passive"))
      (node (ref "D148") (pin "C") (pinfunction "C_C") (pintype "passive"))
      (node (ref "D15") (pin "C") (pinfunction "C_C") (pintype "passive"))
      (node (ref "D155") (pin "C") (pinfunction "C_C") (pintype "passive"))
      (node (ref "D162") (pin "C") (pinfunction "C_C") (pintype "passive"))
      (node (ref "D169") (pin "C") (pinfunction "C_C") (pintype "passive"))
      (node (ref "D22") (pin "C") (pinfunction "C_C") (pintype "passive"))
      (node (ref "D29") (pin "C") (pinfunction "C_C") (pintype "passive"))
      (node (ref "D36") (pin "C") (pinfunction "C_C") (pintype "passive"))
      (node (ref "D43") (pin "C") (pinfunction "C_C") (pintype "passive"))
      (node (ref "D50") (pin "C") (pinfunction "C_C") (pintype "passive"))
      (node (ref "D57") (pin "C") (pinfunction "C_C") (pintype "passive"))
      (node (ref "D64") (pin "C") (pinfunction "C_C") (pintype "passive"))
      (node (ref "D71") (pin "C") (pinfunction "C_C") (pintype "passive"))
      (node (ref "D78") (pin "C") (pinfunction "C_C") (pintype "passive"))
      (node (ref "D8") (pin "C") (pinfunction "C_C") (pintype "passive"))
      (node (ref "D85") (pin "C") (pinfunction "C_C") (pintype "passive"))
      (node (ref "D92") (pin "C") (pinfunction "C_C") (pintype "passive"))
      (node (ref "D99") (pin "C") (pinfunction "C_C") (pintype "passive"))
      (node (ref "Q28") (pin "2") (pinfunction "D_2") (pintype "passive"))
    )
    (net (code "131") (name "ROW1_GATE") (class "Default")
      (node (ref "IC5") (pin "15") (pinfunction "QA_15") (pintype "tri_state"))
      (node (ref "R26") (pin "2") (pinfunction "2_2") (pintype "passive"))
    )
    (net (code "132") (name "ROW2") (class "Default")
      (node (ref "D100") (pin "C") (pinfunction "C_C") (pintype "passive"))
      (node (ref "D107") (pin "C") (pinfunction "C_C") (pintype "passive"))
      (node (ref "D114") (pin "C") (pinfunction "C_C") (pintype "passive"))
      (node (ref "D121") (pin "C") (pinfunction "C_C") (pintype "passive"))
      (node (ref "D128") (pin "C") (pinfunction "C_C") (pintype "passive"))
      (node (ref "D135") (pin "C") (pinfunction "C_C") (pintype "passive"))
      (node (ref "D142") (pin "C") (pinfunction "C_C") (pintype "passive"))
      (node (ref "D149") (pin "C") (pinfunction "C_C") (pintype "passive"))
      (node (ref "D156") (pin "C") (pinfunction "C_C") (pintype "passive"))
      (node (ref "D16") (pin "C") (pinfunction "C_C") (pintype "passive"))
      (node (ref "D163") (pin "C") (pinfunction "C_C") (pintype "passive"))
      (node (ref "D170") (pin "C") (pinfunction "C_C") (pintype "passive"))
      (node (ref "D2") (pin "C") (pinfunction "C_C") (pintype "passive"))
      (node (ref "D23") (pin "C") (pinfunction "C_C") (pintype "passive"))
      (node (ref "D30") (pin "C") (pinfunction "C_C") (pintype "passive"))
      (node (ref "D37") (pin "C") (pinfunction "C_C") (pintype "passive"))
      (node (ref "D44") (pin "C") (pinfunction "C_C") (pintype "passive"))
      (node (ref "D51") (pin "C") (pinfunction "C_C") (pintype "passive"))
      (node (ref "D58") (pin "C") (pinfunction "C_C") (pintype "passive"))
      (node (ref "D65") (pin "C") (pinfunction "C_C") (pintype "passive"))
      (node (ref "D72") (pin "C") (pinfunction "C_C") (pintype "passive"))
      (node (ref "D79") (pin "C") (pinfunction "C_C") (pintype "passive"))
      (node (ref "D86") (pin "C") (pinfunction "C_C") (pintype "passive"))
      (node (ref "D9") (pin "C") (pinfunction "C_C") (pintype "passive"))
      (node (ref "D93") (pin "C") (pinfunction "C_C") (pintype "passive"))
      (node (ref "Q29") (pin "2") (pinfunction "D_2") (pintype "passive"))
    )
    (net (code "133") (name "ROW2_GATE") (class "Default")
      (node (ref "IC5") (pin "1") (pinfunction "QB_1") (pintype "tri_state"))
      (node (ref "R27") (pin "2") (pinfunction "2_2") (pintype "passive"))
    )
    (net (code "134") (name "ROW3") (class "Default")
      (node (ref "D10") (pin "C") (pinfunction "C_C") (pintype "passive"))
      (node (ref "D101") (pin "C") (pinfunction "C_C") (pintype "passive"))
      (node (ref "D108") (pin "C") (pinfunction "C_C") (pintype "passive"))
      (node (ref "D115") (pin "C") (pinfunction "C_C") (pintype "passive"))
      (node (ref "D122") (pin "C") (pinfunction "C_C") (pintype "passive"))
      (node (ref "D129") (pin "C") (pinfunction "C_C") (pintype "passive"))
      (node (ref "D136") (pin "C") (pinfunction "C_C") (pintype "passive"))
      (node (ref "D143") (pin "C") (pinfunction "C_C") (pintype "passive"))
      (node (ref "D150") (pin "C") (pinfunction "C_C") (pintype "passive"))
      (node (ref "D157") (pin "C") (pinfunction "C_C") (pintype "passive"))
      (node (ref "D164") (pin "C") (pinfunction "C_C") (pintype "passive"))
      (node (ref "D17") (pin "C") (pinfunction "C_C") (pintype "passive"))
      (node (ref "D171") (pin "C") (pinfunction "C_C") (pintype "passive"))
      (node (ref "D24") (pin "C") (pinfunction "C_C") (pintype "passive"))
      (node (ref "D3") (pin "C") (pinfunction "C_C") (pintype "passive"))
      (node (ref "D31") (pin "C") (pinfunction "C_C") (pintype "passive"))
      (node (ref "D38") (pin "C") (pinfunction "C_C") (pintype "passive"))
      (node (ref "D45") (pin "C") (pinfunction "C_C") (pintype "passive"))
      (node (ref "D52") (pin "C") (pinfunction "C_C") (pintype "passive"))
      (node (ref "D59") (pin "C") (pinfunction "C_C") (pintype "passive"))
      (node (ref "D66") (pin "C") (pinfunction "C_C") (pintype "passive"))
      (node (ref "D73") (pin "C") (pinfunction "C_C") (pintype "passive"))
      (node (ref "D80") (pin "C") (pinfunction "C_C") (pintype "passive"))
      (node (ref "D87") (pin "C") (pinfunction "C_C") (pintype "passive"))
      (node (ref "D94") (pin "C") (pinfunction "C_C") (pintype "passive"))
      (node (ref "Q30") (pin "2") (pinfunction "D_2") (pintype "passive"))
    )
    (net (code "135") (name "ROW3_GATE") (class "Default")
      (node (ref "IC5") (pin "2") (pinfunction "QC_2") (pintype "tri_state"))
      (node (ref "R28") (pin "2") (pinfunction "2_2") (pintype "passive"))
    )
    (net (code "136") (name "ROW4") (class "Default")
      (node (ref "D102") (pin "C") (pinfunction "C_C") (pintype "passive"))
      (node (ref "D109") (pin "C") (pinfunction "C_C") (pintype "passive"))
      (node (ref "D11") (pin "C") (pinfunction "C_C") (pintype "passive"))
      (node (ref "D116") (pin "C") (pinfunction "C_C") (pintype "passive"))
      (node (ref "D123") (pin "C") (pinfunction "C_C") (pintype "passive"))
      (node (ref "D130") (pin "C") (pinfunction "C_C") (pintype "passive"))
      (node (ref "D137") (pin "C") (pinfunction "C_C") (pintype "passive"))
      (node (ref "D144") (pin "C") (pinfunction "C_C") (pintype "passive"))
      (node (ref "D151") (pin "C") (pinfunction "C_C") (pintype "passive"))
      (node (ref "D158") (pin "C") (pinfunction "C_C") (pintype "passive"))
      (node (ref "D165") (pin "C") (pinfunction "C_C") (pintype "passive"))
      (node (ref "D172") (pin "C") (pinfunction "C_C") (pintype "passive"))
      (node (ref "D18") (pin "C") (pinfunction "C_C") (pintype "passive"))
      (node (ref "D25") (pin "C") (pinfunction "C_C") (pintype "passive"))
      (node (ref "D32") (pin "C") (pinfunction "C_C") (pintype "passive"))
      (node (ref "D39") (pin "C") (pinfunction "C_C") (pintype "passive"))
      (node (ref "D4") (pin "C") (pinfunction "C_C") (pintype "passive"))
      (node (ref "D46") (pin "C") (pinfunction "C_C") (pintype "passive"))
      (node (ref "D53") (pin "C") (pinfunction "C_C") (pintype "passive"))
      (node (ref "D60") (pin "C") (pinfunction "C_C") (pintype "passive"))
      (node (ref "D67") (pin "C") (pinfunction "C_C") (pintype "passive"))
      (node (ref "D74") (pin "C") (pinfunction "C_C") (pintype "passive"))
      (node (ref "D81") (pin "C") (pinfunction "C_C") (pintype "passive"))
      (node (ref "D88") (pin "C") (pinfunction "C_C") (pintype "passive"))
      (node (ref "D95") (pin "C") (pinfunction "C_C") (pintype "passive"))
      (node (ref "Q31") (pin "2") (pinfunction "D_2") (pintype "passive"))
    )
    (net (code "137") (name "ROW4_GATE") (class "Default")
      (node (ref "IC5") (pin "3") (pinfunction "QD_3") (pintype "tri_state"))
      (node (ref "R29") (pin "2") (pinfunction "2_2") (pintype "passive"))
    )
    (net (code "138") (name "ROW5") (class "Default")
      (node (ref "D103") (pin "C") (pinfunction "C_C") (pintype "passive"))
      (node (ref "D110") (pin "C") (pinfunction "C_C") (pintype "passive"))
      (node (ref "D117") (pin "C") (pinfunction "C_C") (pintype "passive"))
      (node (ref "D12") (pin "C") (pinfunction "C_C") (pintype "passive"))
      (node (ref "D124") (pin "C") (pinfunction "C_C") (pintype "passive"))
      (node (ref "D131") (pin "C") (pinfunction "C_C") (pintype "passive"))
      (node (ref "D138") (pin "C") (pinfunction "C_C") (pintype "passive"))
      (node (ref "D145") (pin "C") (pinfunction "C_C") (pintype "passive"))
      (node (ref "D152") (pin "C") (pinfunction "C_C") (pintype "passive"))
      (node (ref "D159") (pin "C") (pinfunction "C_C") (pintype "passive"))
      (node (ref "D166") (pin "C") (pinfunction "C_C") (pintype "passive"))
      (node (ref "D173") (pin "C") (pinfunction "C_C") (pintype "passive"))
      (node (ref "D19") (pin "C") (pinfunction "C_C") (pintype "passive"))
      (node (ref "D26") (pin "C") (pinfunction "C_C") (pintype "passive"))
      (node (ref "D33") (pin "C") (pinfunction "C_C") (pintype "passive"))
      (node (ref "D40") (pin "C") (pinfunction "C_C") (pintype "passive"))
      (node (ref "D47") (pin "C") (pinfunction "C_C") (pintype "passive"))
      (node (ref "D5") (pin "C") (pinfunction "C_C") (pintype "passive"))
      (node (ref "D54") (pin "C") (pinfunction "C_C") (pintype "passive"))
      (node (ref "D61") (pin "C") (pinfunction "C_C") (pintype "passive"))
      (node (ref "D68") (pin "C") (pinfunction "C_C") (pintype "passive"))
      (node (ref "D75") (pin "C") (pinfunction "C_C") (pintype "passive"))
      (node (ref "D82") (pin "C") (pinfunction "C_C") (pintype "passive"))
      (node (ref "D89") (pin "C") (pinfunction "C_C") (pintype "passive"))
      (node (ref "D96") (pin "C") (pinfunction "C_C") (pintype "passive"))
      (node (ref "Q32") (pin "2") (pinfunction "D_2") (pintype "passive"))
    )
    (net (code "139") (name "ROW5_GATE") (class "Default")
      (node (ref "IC5") (pin "4") (pinfunction "QE_4") (pintype "tri_state"))
      (node (ref "R30") (pin "2") (pinfunction "2_2") (pintype "passive"))
    )
    (net (code "140") (name "ROW6") (class "Default")
      (node (ref "D104") (pin "C") (pinfunction "C_C") (pintype "passive"))
      (node (ref "D111") (pin "C") (pinfunction "C_C") (pintype "passive"))
      (node (ref "D118") (pin "C") (pinfunction "C_C") (pintype "passive"))
      (node (ref "D125") (pin "C") (pinfunction "C_C") (pintype "passive"))
      (node (ref "D13") (pin "C") (pinfunction "C_C") (pintype "passive"))
      (node (ref "D132") (pin "C") (pinfunction "C_C") (pintype "passive"))
      (node (ref "D139") (pin "C") (pinfunction "C_C") (pintype "passive"))
      (node (ref "D146") (pin "C") (pinfunction "C_C") (pintype "passive"))
      (node (ref "D153") (pin "C") (pinfunction "C_C") (pintype "passive"))
      (node (ref "D160") (pin "C") (pinfunction "C_C") (pintype "passive"))
      (node (ref "D167") (pin "C") (pinfunction "C_C") (pintype "passive"))
      (node (ref "D174") (pin "C") (pinfunction "C_C") (pintype "passive"))
      (node (ref "D20") (pin "C") (pinfunction "C_C") (pintype "passive"))
      (node (ref "D27") (pin "C") (pinfunction "C_C") (pintype "passive"))
      (node (ref "D34") (pin "C") (pinfunction "C_C") (pintype "passive"))
      (node (ref "D41") (pin "C") (pinfunction "C_C") (pintype "passive"))
      (node (ref "D48") (pin "C") (pinfunction "C_C") (pintype "passive"))
      (node (ref "D55") (pin "C") (pinfunction "C_C") (pintype "passive"))
      (node (ref "D6") (pin "C") (pinfunction "C_C") (pintype "passive"))
      (node (ref "D62") (pin "C") (pinfunction "C_C") (pintype "passive"))
      (node (ref "D69") (pin "C") (pinfunction "C_C") (pintype "passive"))
      (node (ref "D76") (pin "C") (pinfunction "C_C") (pintype "passive"))
      (node (ref "D83") (pin "C") (pinfunction "C_C") (pintype "passive"))
      (node (ref "D90") (pin "C") (pinfunction "C_C") (pintype "passive"))
      (node (ref "D97") (pin "C") (pinfunction "C_C") (pintype "passive"))
      (node (ref "Q33") (pin "2") (pinfunction "D_2") (pintype "passive"))
    )
    (net (code "141") (name "ROW6_GATE") (class "Default")
      (node (ref "IC5") (pin "5") (pinfunction "QF_5") (pintype "tri_state"))
      (node (ref "R31") (pin "2") (pinfunction "2_2") (pintype "passive"))
    )
    (net (code "142") (name "ROW7") (class "Default")
      (node (ref "D105") (pin "C") (pinfunction "C_C") (pintype "passive"))
      (node (ref "D112") (pin "C") (pinfunction "C_C") (pintype "passive"))
      (node (ref "D119") (pin "C") (pinfunction "C_C") (pintype "passive"))
      (node (ref "D126") (pin "C") (pinfunction "C_C") (pintype "passive"))
      (node (ref "D133") (pin "C") (pinfunction "C_C") (pintype "passive"))
      (node (ref "D14") (pin "C") (pinfunction "C_C") (pintype "passive"))
      (node (ref "D140") (pin "C") (pinfunction "C_C") (pintype "passive"))
      (node (ref "D147") (pin "C") (pinfunction "C_C") (pintype "passive"))
      (node (ref "D154") (pin "C") (pinfunction "C_C") (pintype "passive"))
      (node (ref "D161") (pin "C") (pinfunction "C_C") (pintype "passive"))
      (node (ref "D168") (pin "C") (pinfunction "C_C") (pintype "passive"))
      (node (ref "D175") (pin "C") (pinfunction "C_C") (pintype "passive"))
      (node (ref "D21") (pin "C") (pinfunction "C_C") (pintype "passive"))
      (node (ref "D28") (pin "C") (pinfunction "C_C") (pintype "passive"))
      (node (ref "D35") (pin "C") (pinfunction "C_C") (pintype "passive"))
      (node (ref "D42") (pin "C") (pinfunction "C_C") (pintype "passive"))
      (node (ref "D49") (pin "C") (pinfunction "C_C") (pintype "passive"))
      (node (ref "D56") (pin "C") (pinfunction "C_C") (pintype "passive"))
      (node (ref "D63") (pin "C") (pinfunction "C_C") (pintype "passive"))
      (node (ref "D7") (pin "C") (pinfunction "C_C") (pintype "passive"))
      (node (ref "D70") (pin "C") (pinfunction "C_C") (pintype "passive"))
      (node (ref "D77") (pin "C") (pinfunction "C_C") (pintype "passive"))
      (node (ref "D84") (pin "C") (pinfunction "C_C") (pintype "passive"))
      (node (ref "D91") (pin "C") (pinfunction "C_C") (pintype "passive"))
      (node (ref "D98") (pin "C") (pinfunction "C_C") (pintype "passive"))
      (node (ref "Q34") (pin "2") (pinfunction "D_2") (pintype "passive"))
    )
    (net (code "143") (name "ROW7_GATE") (class "Default")
      (node (ref "IC5") (pin "6") (pinfunction "QG_6") (pintype "tri_state"))
      (node (ref "R32") (pin "2") (pinfunction "2_2") (pintype "passive"))
    )
    (net (code "144") (name "V+") (class "Default")
      (node (ref "C15") (pin "1") (pinfunction "1_1") (pintype "passive"))
      (node (ref "C21") (pin "1") (pinfunction "1_1") (pintype "passive"))
      (node (ref "P1") (pin "1") (pinfunction "1_1") (pintype "passive"))
      (node (ref "P3") (pin "1") (pinfunction "1_1") (pintype "passive"))
      (node (ref "Q26") (pin "D1") (pinfunction "D1_D1") (pintype "passive"))
      (node (ref "Q26") (pin "D2") (pinfunction "D2_D2") (pintype "passive"))
      (node (ref "Q26") (pin "D3") (pinfunction "D3_D3") (pintype "passive"))
      (node (ref "Q26") (pin "D4") (pinfunction "D4_D4") (pintype "passive"))
      (node (ref "R94") (pin "2") (pinfunction "2_2") (pintype "passive"))
      (node (ref "U4") (pin "2") (pinfunction "VIN_2") (pintype "bidirectional"))
    )
    (net (code "145") (name "VCC_A") (class "Default")
      (node (ref "C6") (pin "1") (pinfunction "1_1") (pintype "passive"))
      (node (ref "U1") (pin "1") (pinfunction "VCCA_1") (pintype "bidirectional"))
      (node (ref "U1") (pin "8") (pinfunction "OE_8") (pintype "bidirectional"))
      (node (ref "U2") (pin "2") (pinfunction "OUT_2") (pintype "output"))
    )
    (net (code "146") (name "VDD") (class "Default")
      (node (ref "C1") (pin "1") (pinfunction "1_1") (pintype "passive"))
      (node (ref "C19") (pin "1") (pinfunction "1_1") (pintype "passive"))
      (node (ref "C2") (pin "1") (pinfunction "1_1") (pintype "passive"))
      (node (ref "C20") (pin "1") (pinfunction "1_1") (pintype "passive"))
      (node (ref "C3") (pin "1") (pinfunction "1_1") (pintype "passive"))
      (node (ref "C4") (pin "1") (pinfunction "1_1") (pintype "passive"))
      (node (ref "C5") (pin "1") (pinfunction "1_1") (pintype "passive"))
      (node (ref "C7") (pin "1") (pinfunction "1_1") (pintype "passive"))
      (node (ref "IC5") (pin "10") (pinfunction "SCL_10") (pintype "input"))
      (node (ref "IC5") (pin "16") (pinfunction "VCC_16") (pintype "power_in"))
      (node (ref "IC6") (pin "10") (pinfunction "SCL_10") (pintype "input"))
      (node (ref "IC6") (pin "16") (pinfunction "VCC_16") (pintype "power_in"))
      (node (ref "IC7") (pin "10") (pinfunction "SCL_10") (pintype "input"))
      (node (ref "IC7") (pin "16") (pinfunction "VCC_16") (pintype "power_in"))
      (node (ref "IC8") (pin "10") (pinfunction "SCL_10") (pintype "input"))
      (node (ref "IC8") (pin "16") (pinfunction "VCC_16") (pintype "power_in"))
      (node (ref "JP2") (pin "9") (pinfunction "9_9") (pintype "passive"))
      (node (ref "JP3") (pin "9") (pinfunction "9_9") (pintype "passive"))
      (node (ref "L2") (pin "P$2") (pinfunction "2_P$2") (pintype "passive"))
      (node (ref "Q1") (pin "2") (pinfunction "S_2") (pintype "passive"))
      (node (ref "Q10") (pin "2") (pinfunction "S_2") (pintype "passive"))
      (node (ref "Q11") (pin "2") (pinfunction "S_2") (pintype "passive"))
      (node (ref "Q12") (pin "2") (pinfunction "S_2") (pintype "passive"))
      (node (ref "Q13") (pin "2") (pinfunction "S_2") (pintype "passive"))
      (node (ref "Q14") (pin "2") (pinfunction "S_2") (pintype "passive"))
      (node (ref "Q15") (pin "2") (pinfunction "S_2") (pintype "passive"))
      (node (ref "Q16") (pin "2") (pinfunction "S_2") (pintype "passive"))
      (node (ref "Q17") (pin "2") (pinfunction "S_2") (pintype "passive"))
      (node (ref "Q18") (pin "2") (pinfunction "S_2") (pintype "passive"))
      (node (ref "Q19") (pin "2") (pinfunction "S_2") (pintype "passive"))
      (node (ref "Q2") (pin "2") (pinfunction "S_2") (pintype "passive"))
      (node (ref "Q20") (pin "2") (pinfunction "S_2") (pintype "passive"))
      (node (ref "Q21") (pin "2") (pinfunction "S_2") (pintype "passive"))
      (node (ref "Q22") (pin "2") (pinfunction "S_2") (pintype "passive"))
      (node (ref "Q23") (pin "2") (pinfunction "S_2") (pintype "passive"))
      (node (ref "Q24") (pin "2") (pinfunction "S_2") (pintype "passive"))
      (node (ref "Q25") (pin "2") (pinfunction "S_2") (pintype "passive"))
      (node (ref "Q3") (pin "2") (pinfunction "S_2") (pintype "passive"))
      (node (ref "Q4") (pin "2") (pinfunction "S_2") (pintype "passive"))
      (node (ref "Q5") (pin "2") (pinfunction "S_2") (pintype "passive"))
      (node (ref "Q6") (pin "2") (pinfunction "S_2") (pintype "passive"))
      (node (ref "Q7") (pin "2") (pinfunction "S_2") (pintype "passive"))
      (node (ref "Q8") (pin "2") (pinfunction "S_2") (pintype "passive"))
      (node (ref "Q9") (pin "2") (pinfunction "S_2") (pintype "passive"))
      (node (ref "R53") (pin "2") (pinfunction "2_2") (pintype "passive"))
      (node (ref "R54") (pin "2") (pinfunction "2_2") (pintype "passive"))
      (node (ref "R55") (pin "2") (pinfunction "2_2") (pintype "passive"))
      (node (ref "R56") (pin "2") (pinfunction "2_2") (pintype "passive"))
      (node (ref "R57") (pin "2") (pinfunction "2_2") (pintype "passive"))
      (node (ref "R58") (pin "2") (pinfunction "2_2") (pintype "passive"))
      (node (ref "R59") (pin "2") (pinfunction "2_2") (pintype "passive"))
      (node (ref "R60") (pin "2") (pinfunction "2_2") (pintype "passive"))
      (node (ref "R61") (pin "2") (pinfunction "2_2") (pintype "passive"))
      (node (ref "R62") (pin "2") (pinfunction "2_2") (pintype "passive"))
      (node (ref "R63") (pin "2") (pinfunction "2_2") (pintype "passive"))
      (node (ref "R64") (pin "2") (pinfunction "2_2") (pintype "passive"))
      (node (ref "R65") (pin "2") (pinfunction "2_2") (pintype "passive"))
      (node (ref "R66") (pin "2") (pinfunction "2_2") (pintype "passive"))
      (node (ref "R67") (pin "2") (pinfunction "2_2") (pintype "passive"))
      (node (ref "R68") (pin "2") (pinfunction "2_2") (pintype "passive"))
      (node (ref "R69") (pin "2") (pinfunction "2_2") (pintype "passive"))
      (node (ref "R70") (pin "2") (pinfunction "2_2") (pintype "passive"))
      (node (ref "R71") (pin "2") (pinfunction "2_2") (pintype "passive"))
      (node (ref "R72") (pin "2") (pinfunction "2_2") (pintype "passive"))
      (node (ref "R78") (pin "2") (pinfunction "2_2") (pintype "passive"))
      (node (ref "R79") (pin "2") (pinfunction "2_2") (pintype "passive"))
      (node (ref "R80") (pin "2") (pinfunction "2_2") (pintype "passive"))
      (node (ref "R81") (pin "2") (pinfunction "2_2") (pintype "passive"))
      (node (ref "R82") (pin "2") (pinfunction "2_2") (pintype "passive"))
      (node (ref "R93") (pin "1") (pinfunction "1_1") (pintype "passive"))
      (node (ref "R96") (pin "2") (pinfunction "2_2") (pintype "passive"))
      (node (ref "U1") (pin "14") (pinfunction "VCCB_14") (pintype "bidirectional"))
      (node (ref "U2") (pin "3") (pinfunction "IN_3") (pintype "input"))
    )
    (net (code "147") (name "unconnected-(JP2-Pad5)") (class "Default")
      (node (ref "JP2") (pin "5") (pinfunction "5_5") (pintype "passive"))
    )
    (net (code "148") (name "unconnected-(JP2-Pad6)") (class "Default")
      (node (ref "JP2") (pin "6") (pinfunction "6_6") (pintype "passive"))
    )
    (net (code "149") (name "unconnected-(JP2-Pad7)") (class "Default")
      (node (ref "JP2") (pin "7") (pinfunction "7_7") (pintype "passive"))
    )
    (net (code "150") (name "unconnected-(JP2-Pad8)") (class "Default")
      (node (ref "JP2") (pin "8") (pinfunction "8_8") (pintype "passive"))
    )
    (net (code "151") (name "unconnected-(JP3-Pad5)") (class "Default")
      (node (ref "JP3") (pin "5") (pinfunction "5_5") (pintype "passive"))
    )
    (net (code "152") (name "unconnected-(JP3-Pad6)") (class "Default")
      (node (ref "JP3") (pin "6") (pinfunction "6_6") (pintype "passive"))
    )
    (net (code "153") (name "unconnected-(JP3-Pad7)") (class "Default")
      (node (ref "JP3") (pin "7") (pinfunction "7_7") (pintype "passive"))
    )
    (net (code "154") (name "unconnected-(JP3-Pad8)") (class "Default")
      (node (ref "JP3") (pin "8") (pinfunction "8_8") (pintype "passive"))
    )
    (net (code "155") (name "unconnected-(U4-EN-Pad3)") (class "Default")
      (node (ref "U4") (pin "3") (pinfunction "EN_3") (pintype "bidirectional"))
    )
  )
)
